# senseBox-MCU_v11.net
KiCad netlist of a schematic drawn in EAGLE
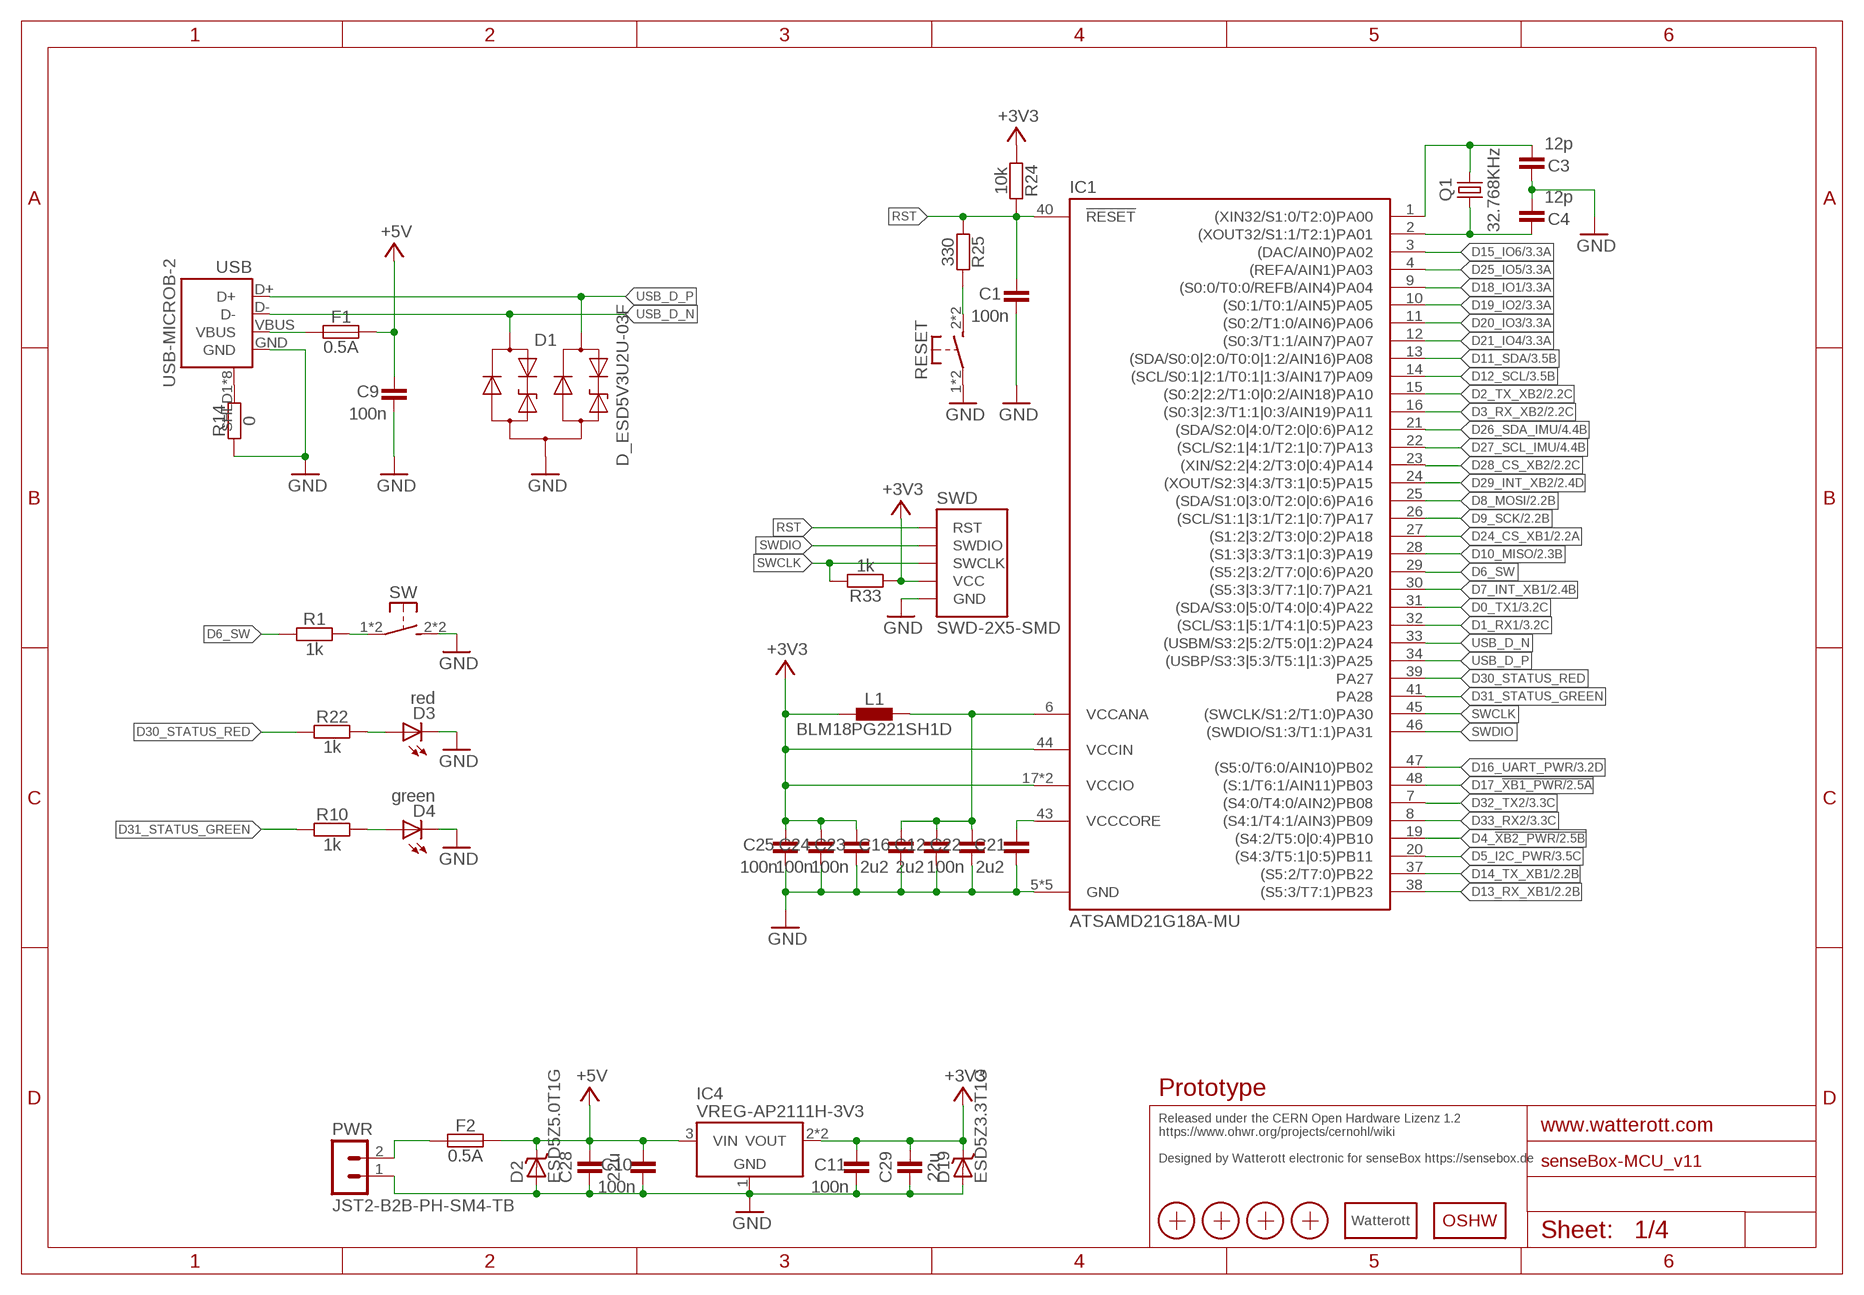
[diagram p0: schematic, sheet 1]
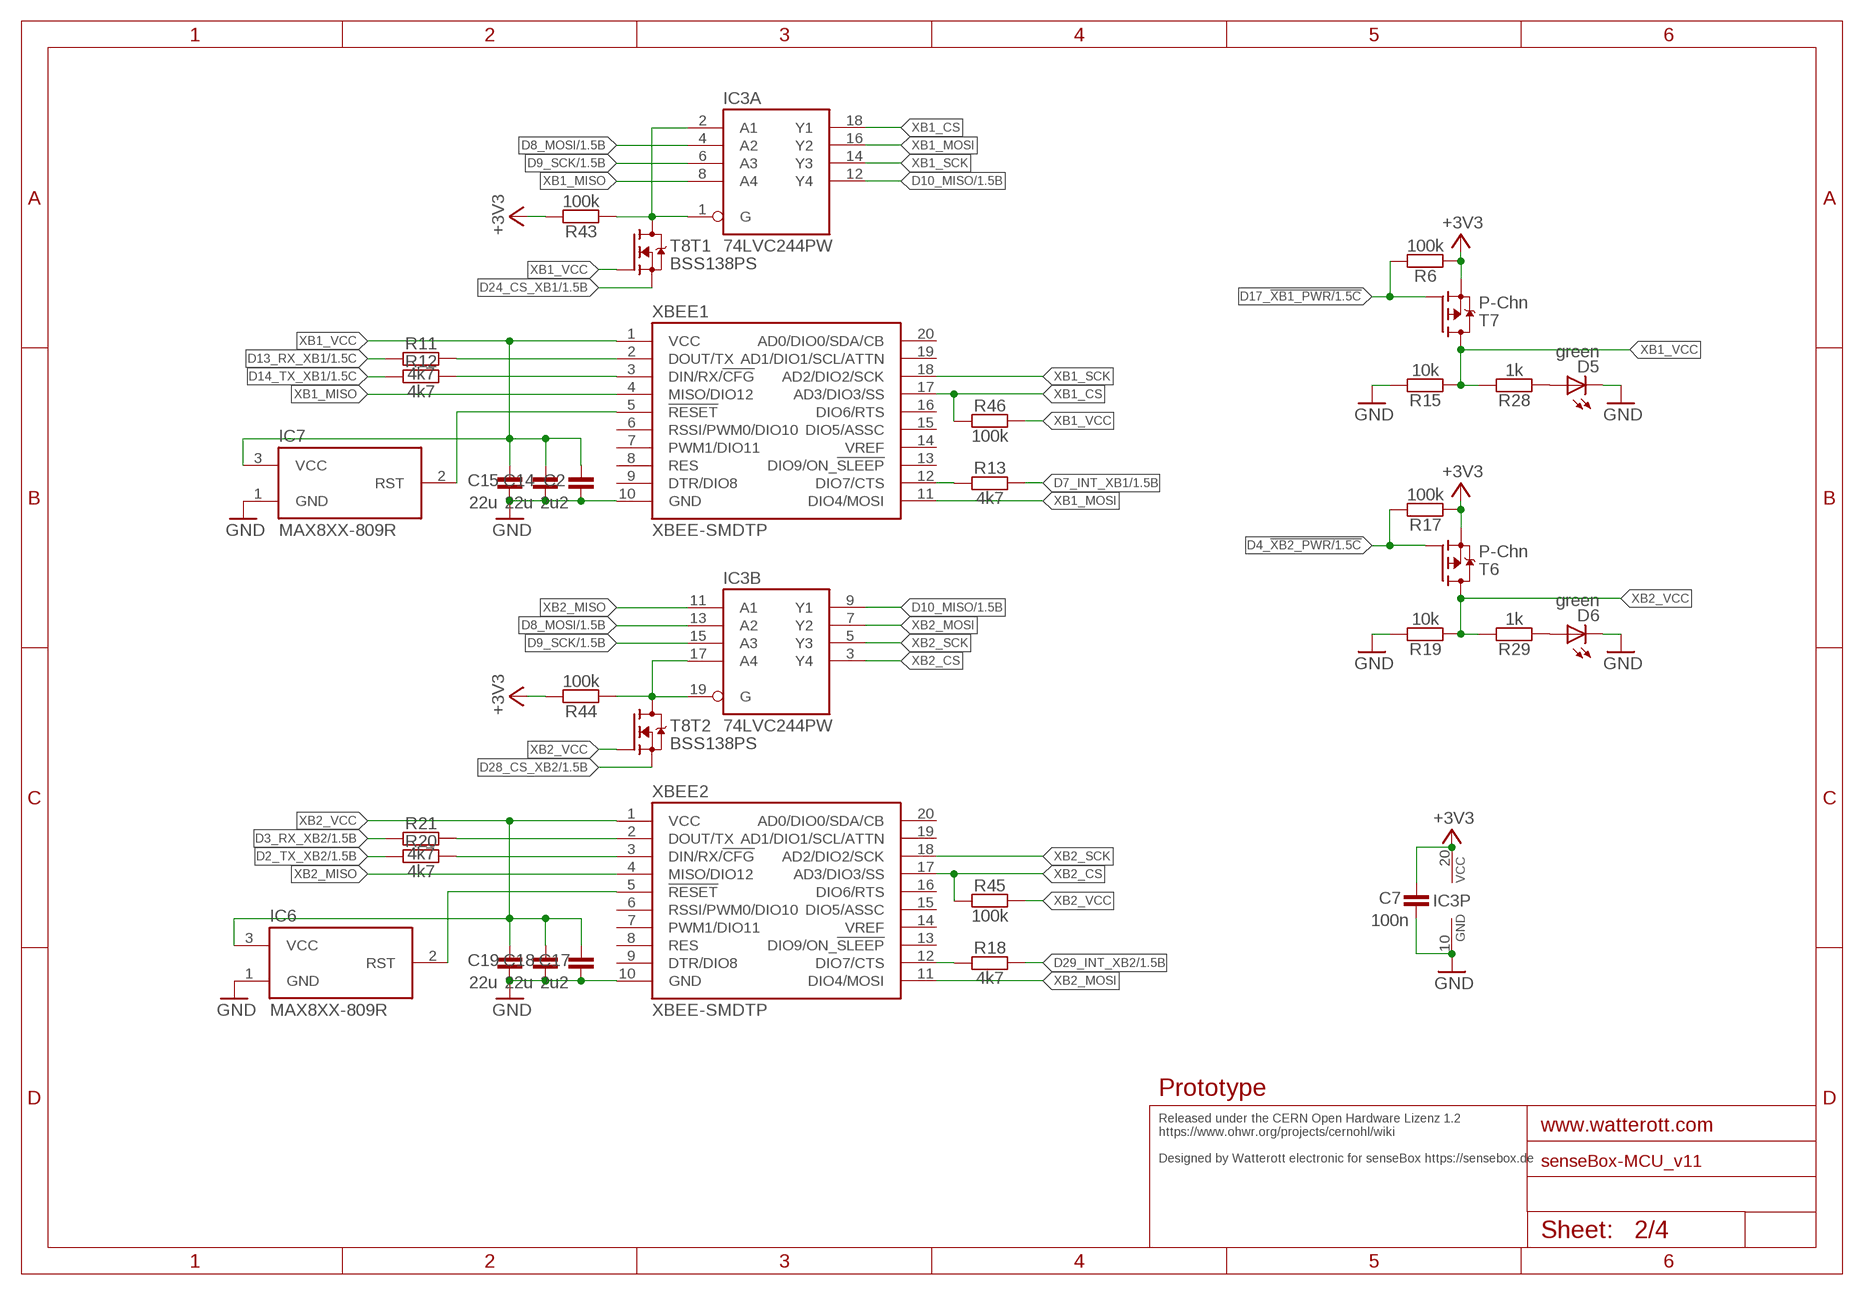
[diagram p1: schematic, sheet 2]
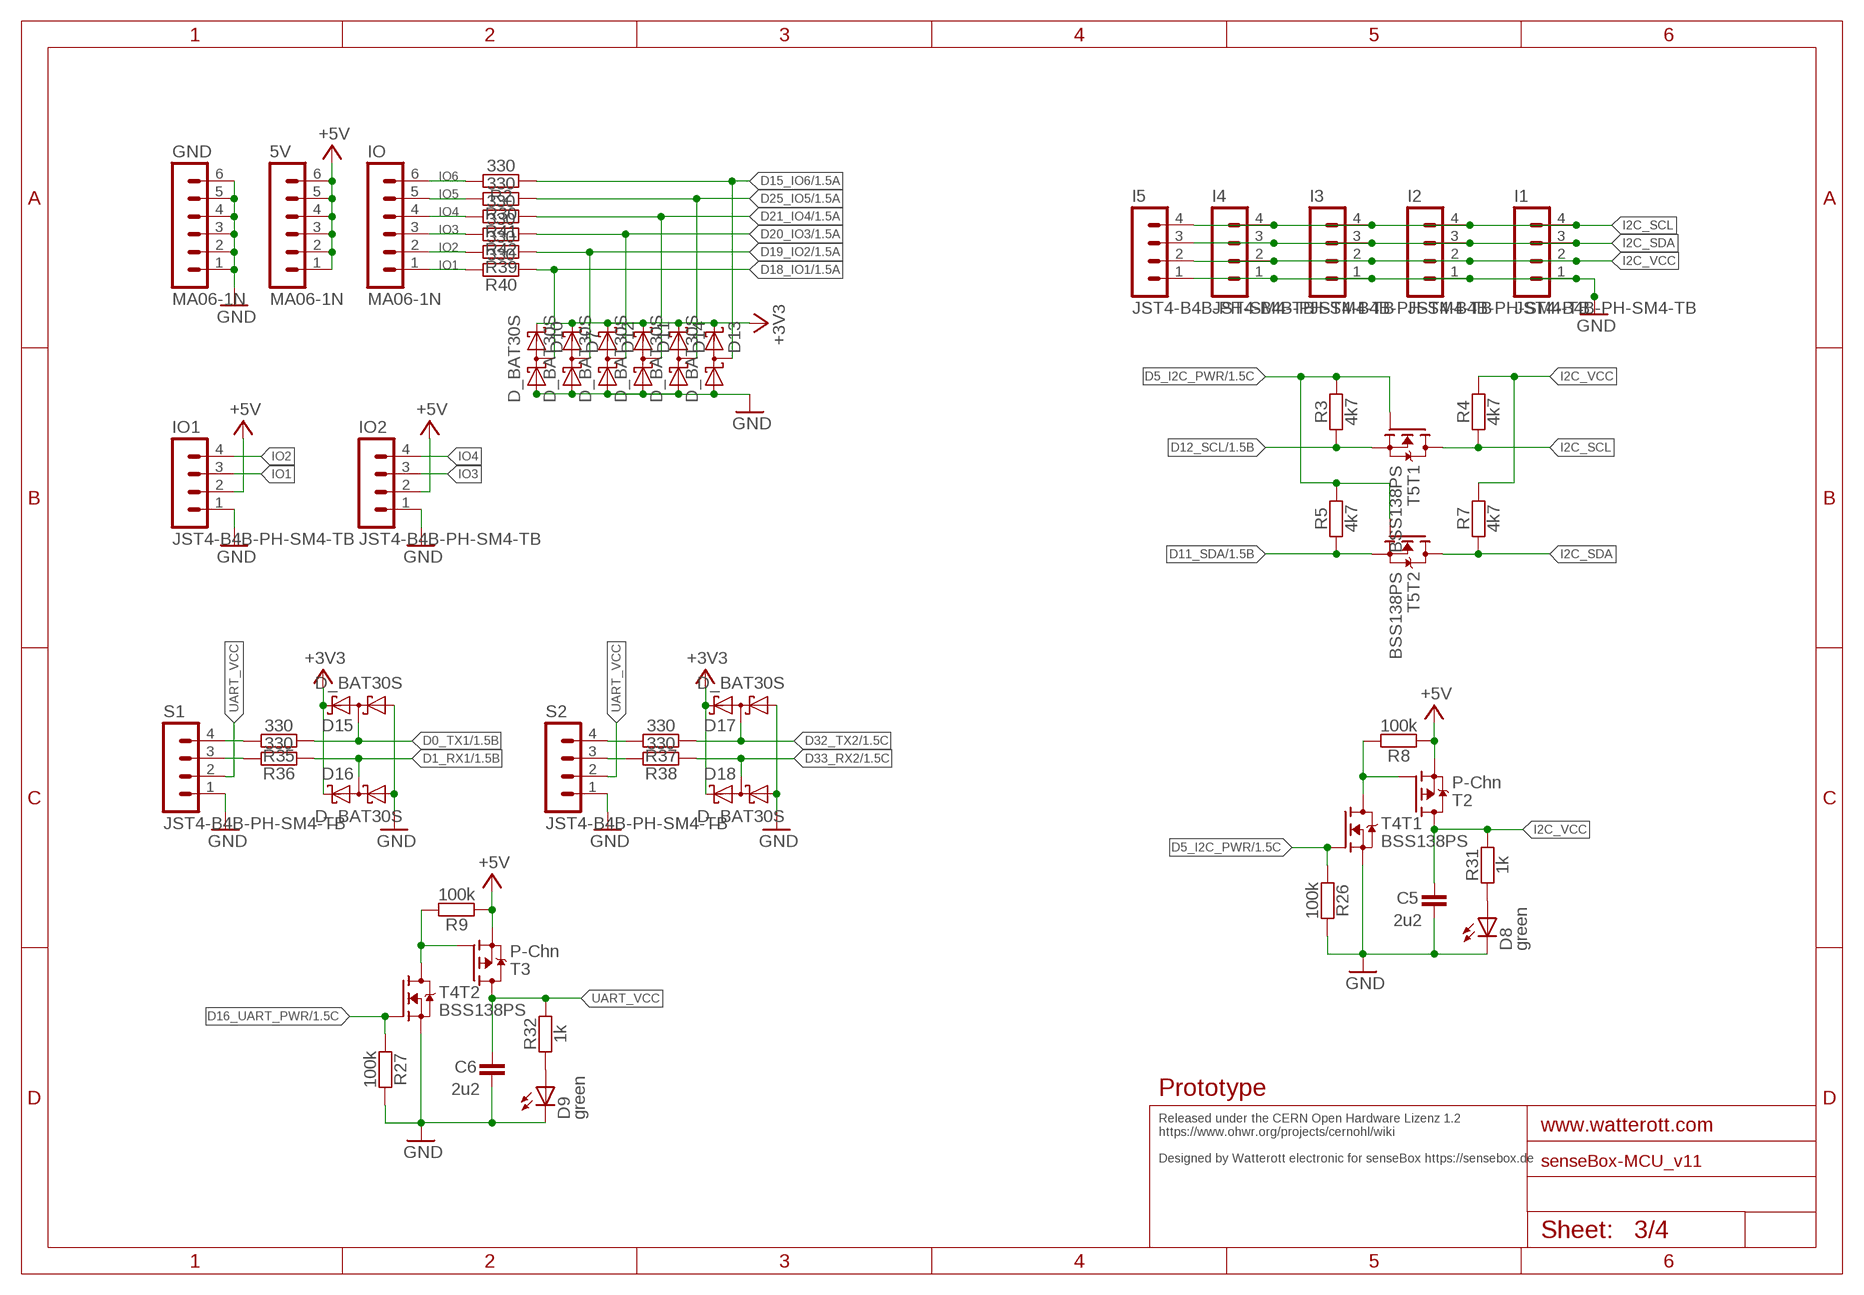
[diagram p2: schematic, sheet 3]
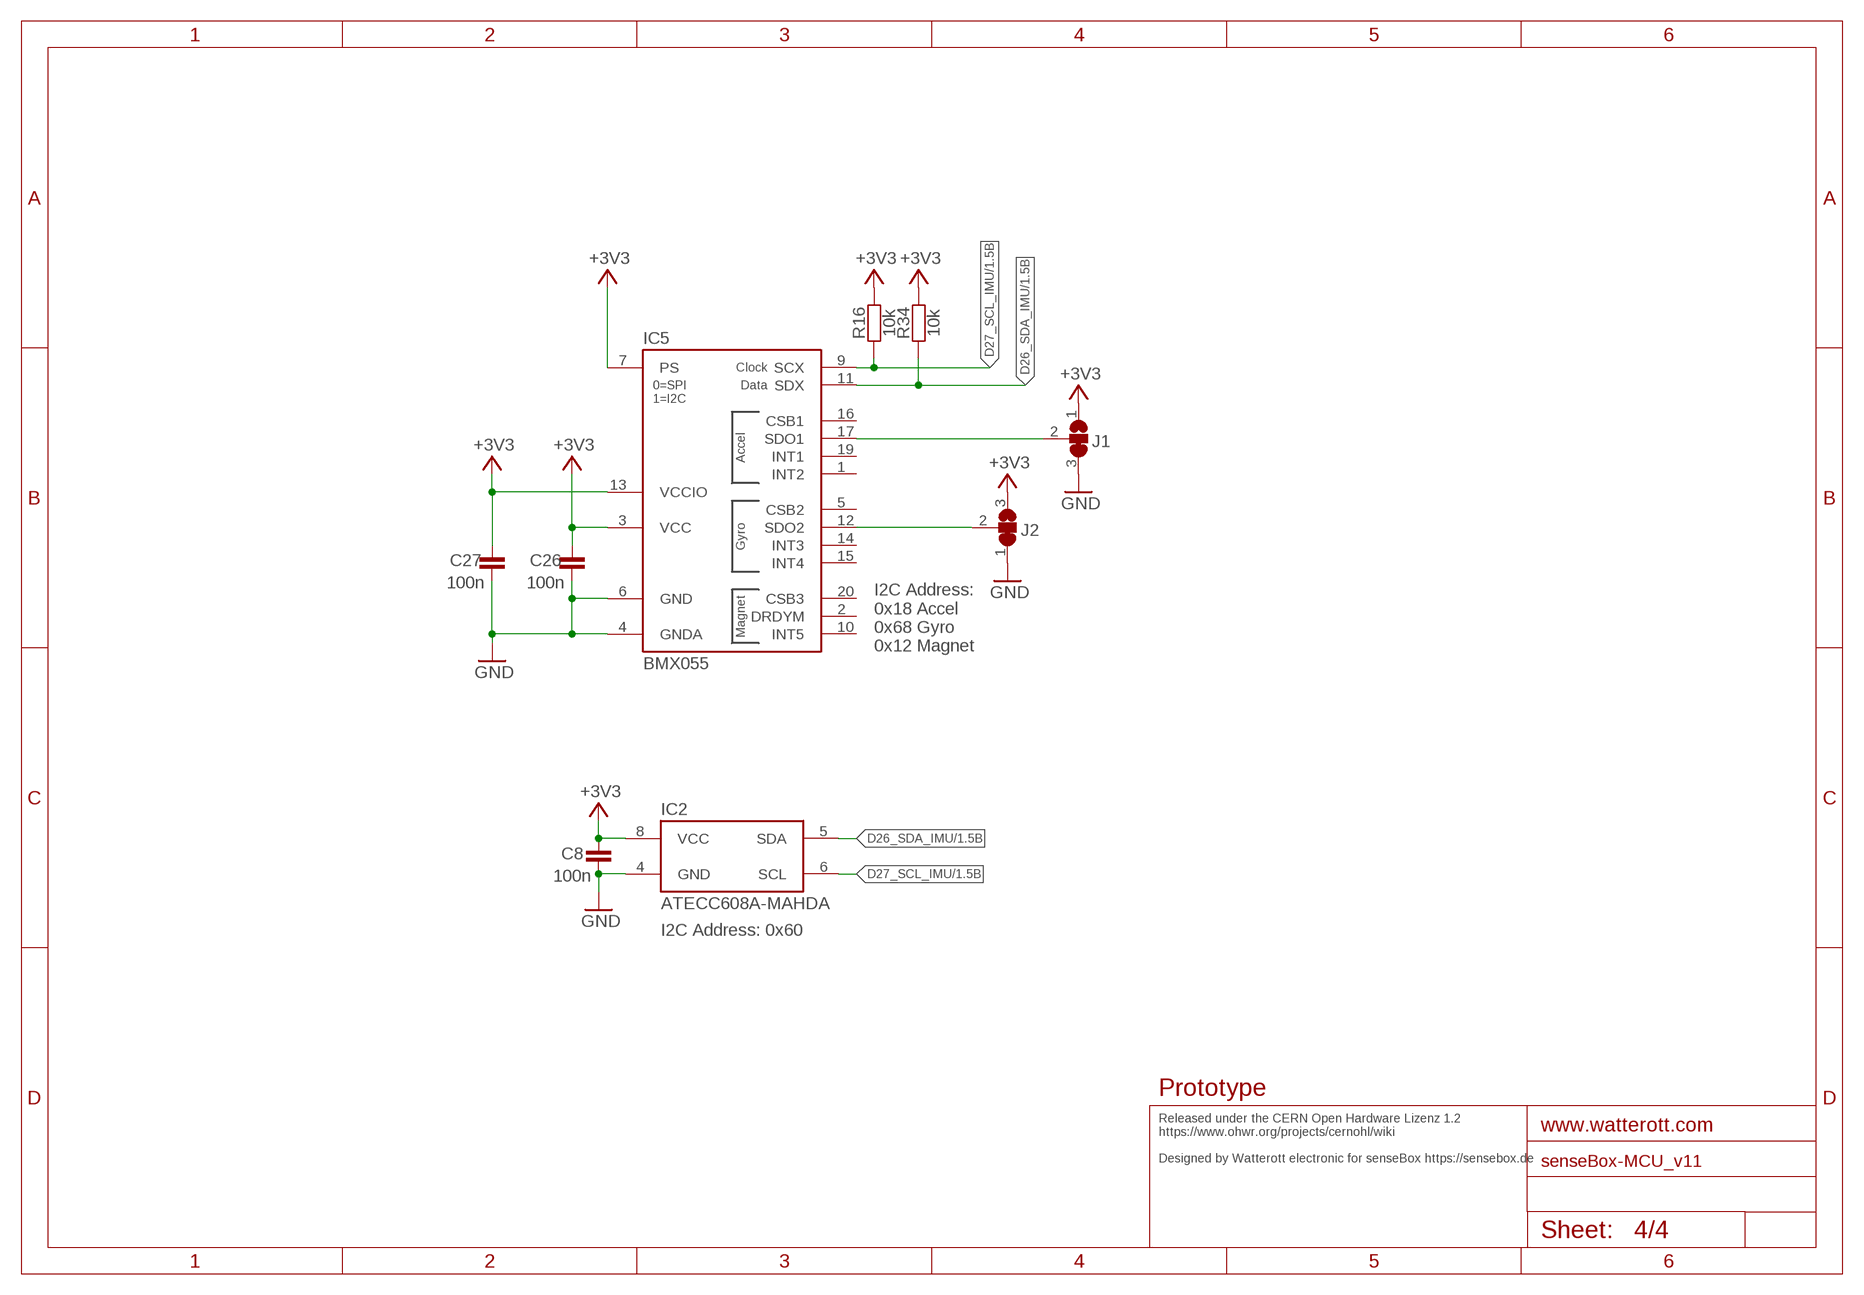
[diagram p3: schematic, sheet 4]

(export (version "E")
  (design (tool "Eeschema 10.0.6"))
  (components
    (comp (ref "C8")
      (value "100n")
      (footprint "eagle-import:C0402")
      (libsource (lib "eagle-import") (part "CAPACITOR-0402"))
    )
    (comp (ref "C26")
      (value "100n")
      (footprint "eagle-import:C0402")
      (libsource (lib "eagle-import") (part "CAPACITOR-0402"))
    )
    (comp (ref "C27")
      (value "100n")
      (footprint "eagle-import:C0402")
      (libsource (lib "eagle-import") (part "CAPACITOR-0402"))
    )
    (comp (ref "IC2")
      (value "ATECC608A-MAHDA")
      (footprint "eagle-import:UDFN8")
      (libsource (lib "eagle-import") (part "ATECC508A-MAHDA"))
    )
    (comp (ref "IC5")
      (value "BMX055")
      (footprint "eagle-import:BMX055")
      (libsource (lib "eagle-import") (part "BMX055"))
    )
    (comp (ref "J1")
      (value "JUMPER3-0402")
      (footprint "eagle-import:JUMPER3-0402")
      (libsource (lib "eagle-import") (part "JUMPER3-0402"))
    )
    (comp (ref "J2")
      (value "JUMPER3-0402")
      (footprint "eagle-import:JUMPER3-0402")
      (libsource (lib "eagle-import") (part "JUMPER3-0402"))
    )
    (comp (ref "R16")
      (value "10k")
      (footprint "eagle-import:C0402")
      (libsource (lib "eagle-import") (part "RESISTOR-0402"))
    )
    (comp (ref "R34")
      (value "10k")
      (footprint "eagle-import:C0402")
      (libsource (lib "eagle-import") (part "RESISTOR-0402"))
    )
    (comp (ref "5V")
      (value "MA06-1N")
      (footprint "eagle-import:MA06-1_N")
      (libsource (lib "eagle-import") (part "MA06-1N"))
    )
    (comp (ref "C5")
      (value "2u2")
      (footprint "eagle-import:C0402")
      (libsource (lib "eagle-import") (part "CAPACITOR-0402"))
    )
    (comp (ref "C6")
      (value "2u2")
      (footprint "eagle-import:C0402")
      (libsource (lib "eagle-import") (part "CAPACITOR-0402"))
    )
    (comp (ref "D7")
      (value "D_BAT30S")
      (footprint "eagle-import:SOT323")
      (libsource (lib "eagle-import") (part "D_BAT30S"))
    )
    (comp (ref "D8")
      (value "green")
      (footprint "eagle-import:C0603")
      (libsource (lib "eagle-import") (part "LED-0603"))
    )
    (comp (ref "D9")
      (value "green")
      (footprint "eagle-import:C0603")
      (libsource (lib "eagle-import") (part "LED-0603"))
    )
    (comp (ref "D10")
      (value "D_BAT30S")
      (footprint "eagle-import:SOT323")
      (libsource (lib "eagle-import") (part "D_BAT30S"))
    )
    (comp (ref "D11")
      (value "D_BAT30S")
      (footprint "eagle-import:SOT323")
      (libsource (lib "eagle-import") (part "D_BAT30S"))
    )
    (comp (ref "D12")
      (value "D_BAT30S")
      (footprint "eagle-import:SOT323")
      (libsource (lib "eagle-import") (part "D_BAT30S"))
    )
    (comp (ref "D13")
      (value "D_BAT30S")
      (footprint "eagle-import:SOT323")
      (libsource (lib "eagle-import") (part "D_BAT30S"))
    )
    (comp (ref "D14")
      (value "D_BAT30S")
      (footprint "eagle-import:SOT323")
      (libsource (lib "eagle-import") (part "D_BAT30S"))
    )
    (comp (ref "D15")
      (value "D_BAT30S")
      (footprint "eagle-import:SOT323")
      (libsource (lib "eagle-import") (part "D_BAT30S"))
    )
    (comp (ref "D16")
      (value "D_BAT30S")
      (footprint "eagle-import:SOT323")
      (libsource (lib "eagle-import") (part "D_BAT30S"))
    )
    (comp (ref "D17")
      (value "D_BAT30S")
      (footprint "eagle-import:SOT323")
      (libsource (lib "eagle-import") (part "D_BAT30S"))
    )
    (comp (ref "D18")
      (value "D_BAT30S")
      (footprint "eagle-import:SOT323")
      (libsource (lib "eagle-import") (part "D_BAT30S"))
    )
    (comp (ref "GND")
      (value "MA06-1N")
      (footprint "eagle-import:MA06-1_N")
      (libsource (lib "eagle-import") (part "MA06-1N"))
    )
    (comp (ref "I1")
      (value "JST4-B4B-PH-SM4-TB")
      (footprint "eagle-import:JST_B4B-PH-SM4-TB")
      (libsource (lib "eagle-import") (part "JST4-B4B-PH-SM4-TB"))
    )
    (comp (ref "I2")
      (value "JST4-B4B-PH-SM4-TB")
      (footprint "eagle-import:JST_B4B-PH-SM4-TB")
      (libsource (lib "eagle-import") (part "JST4-B4B-PH-SM4-TB"))
    )
    (comp (ref "I3")
      (value "JST4-B4B-PH-SM4-TB")
      (footprint "eagle-import:JST_B4B-PH-SM4-TB")
      (libsource (lib "eagle-import") (part "JST4-B4B-PH-SM4-TB"))
    )
    (comp (ref "I4")
      (value "JST4-B4B-PH-SM4-TB")
      (footprint "eagle-import:JST_B4B-PH-SM4-TB")
      (libsource (lib "eagle-import") (part "JST4-B4B-PH-SM4-TB"))
    )
    (comp (ref "I5")
      (value "JST4-B4B-PH-SM4-TB")
      (footprint "eagle-import:JST_B4B-PH-SM4-TB")
      (libsource (lib "eagle-import") (part "JST4-B4B-PH-SM4-TB"))
    )
    (comp (ref "IO")
      (value "MA06-1N")
      (footprint "eagle-import:MA06-1_N")
      (libsource (lib "eagle-import") (part "MA06-1N"))
    )
    (comp (ref "IO1")
      (value "JST4-B4B-PH-SM4-TB")
      (footprint "eagle-import:JST_B4B-PH-SM4-TB")
      (libsource (lib "eagle-import") (part "JST4-B4B-PH-SM4-TB"))
    )
    (comp (ref "IO2")
      (value "JST4-B4B-PH-SM4-TB")
      (footprint "eagle-import:JST_B4B-PH-SM4-TB")
      (libsource (lib "eagle-import") (part "JST4-B4B-PH-SM4-TB"))
    )
    (comp (ref "R2")
      (value "330")
      (footprint "eagle-import:C0402")
      (libsource (lib "eagle-import") (part "RESISTOR-0402"))
    )
    (comp (ref "R3")
      (value "4k7")
      (footprint "eagle-import:C0402")
      (libsource (lib "eagle-import") (part "RESISTOR-0402"))
    )
    (comp (ref "R4")
      (value "4k7")
      (footprint "eagle-import:C0402")
      (libsource (lib "eagle-import") (part "RESISTOR-0402"))
    )
    (comp (ref "R5")
      (value "4k7")
      (footprint "eagle-import:C0402")
      (libsource (lib "eagle-import") (part "RESISTOR-0402"))
    )
    (comp (ref "R7")
      (value "4k7")
      (footprint "eagle-import:C0402")
      (libsource (lib "eagle-import") (part "RESISTOR-0402"))
    )
    (comp (ref "R8")
      (value "100k")
      (footprint "eagle-import:C0402")
      (libsource (lib "eagle-import") (part "RESISTOR-0402"))
    )
    (comp (ref "R9")
      (value "100k")
      (footprint "eagle-import:C0402")
      (libsource (lib "eagle-import") (part "RESISTOR-0402"))
    )
    (comp (ref "R26")
      (value "100k")
      (footprint "eagle-import:C0402")
      (libsource (lib "eagle-import") (part "RESISTOR-0402"))
    )
    (comp (ref "R27")
      (value "100k")
      (footprint "eagle-import:C0402")
      (libsource (lib "eagle-import") (part "RESISTOR-0402"))
    )
    (comp (ref "R30")
      (value "330")
      (footprint "eagle-import:C0402")
      (libsource (lib "eagle-import") (part "RESISTOR-0402"))
    )
    (comp (ref "R31")
      (value "1k")
      (footprint "eagle-import:C0402")
      (libsource (lib "eagle-import") (part "RESISTOR-0402"))
    )
    (comp (ref "R32")
      (value "1k")
      (footprint "eagle-import:C0402")
      (libsource (lib "eagle-import") (part "RESISTOR-0402"))
    )
    (comp (ref "R35")
      (value "330")
      (footprint "eagle-import:C0402")
      (libsource (lib "eagle-import") (part "RESISTOR-0402"))
    )
    (comp (ref "R36")
      (value "330")
      (footprint "eagle-import:C0402")
      (libsource (lib "eagle-import") (part "RESISTOR-0402"))
    )
    (comp (ref "R37")
      (value "330")
      (footprint "eagle-import:C0402")
      (libsource (lib "eagle-import") (part "RESISTOR-0402"))
    )
    (comp (ref "R38")
      (value "330")
      (footprint "eagle-import:C0402")
      (libsource (lib "eagle-import") (part "RESISTOR-0402"))
    )
    (comp (ref "R39")
      (value "330")
      (footprint "eagle-import:C0402")
      (libsource (lib "eagle-import") (part "RESISTOR-0402"))
    )
    (comp (ref "R40")
      (value "330")
      (footprint "eagle-import:C0402")
      (libsource (lib "eagle-import") (part "RESISTOR-0402"))
    )
    (comp (ref "R41")
      (value "330")
      (footprint "eagle-import:C0402")
      (libsource (lib "eagle-import") (part "RESISTOR-0402"))
    )
    (comp (ref "R42")
      (value "330")
      (footprint "eagle-import:C0402")
      (libsource (lib "eagle-import") (part "RESISTOR-0402"))
    )
    (comp (ref "S1")
      (value "JST4-B4B-PH-SM4-TB")
      (footprint "eagle-import:JST_B4B-PH-SM4-TB")
      (libsource (lib "eagle-import") (part "JST4-B4B-PH-SM4-TB"))
    )
    (comp (ref "S2")
      (value "JST4-B4B-PH-SM4-TB")
      (footprint "eagle-import:JST_B4B-PH-SM4-TB")
      (libsource (lib "eagle-import") (part "JST4-B4B-PH-SM4-TB"))
    )
    (comp (ref "T2")
      (value "P-Chn")
      (footprint "eagle-import:SOT23")
      (libsource (lib "eagle-import") (part "MOSFET-P-SOT23"))
    )
    (comp (ref "T3")
      (value "P-Chn")
      (footprint "eagle-import:SOT23")
      (libsource (lib "eagle-import") (part "MOSFET-P-SOT23"))
    )
    (comp (ref "T4")
      (value "BSS138PS")
      (footprint "eagle-import:SOT363")
      (libsource (lib "eagle-import") (part "BSS138PS"))
    )
    (comp (ref "T5")
      (value "BSS138PS")
      (footprint "eagle-import:SOT363")
      (libsource (lib "eagle-import") (part "BSS138PS"))
    )
    (comp (ref "C2")
      (value "2u2")
      (footprint "eagle-import:C0402")
      (libsource (lib "eagle-import") (part "CAPACITOR-0402"))
    )
    (comp (ref "C7")
      (value "100n")
      (footprint "eagle-import:C0402")
      (libsource (lib "eagle-import") (part "CAPACITOR-0402"))
    )
    (comp (ref "C14")
      (value "22u")
      (footprint "eagle-import:C0805")
      (libsource (lib "eagle-import") (part "CAPACITOR-0805"))
    )
    (comp (ref "C15")
      (value "22u")
      (footprint "eagle-import:C0805")
      (libsource (lib "eagle-import") (part "CAPACITOR-0805"))
    )
    (comp (ref "C17")
      (value "2u2")
      (footprint "eagle-import:C0402")
      (libsource (lib "eagle-import") (part "CAPACITOR-0402"))
    )
    (comp (ref "C18")
      (value "22u")
      (footprint "eagle-import:C0805")
      (libsource (lib "eagle-import") (part "CAPACITOR-0805"))
    )
    (comp (ref "C19")
      (value "22u")
      (footprint "eagle-import:C0805")
      (libsource (lib "eagle-import") (part "CAPACITOR-0805"))
    )
    (comp (ref "D5")
      (value "green")
      (footprint "eagle-import:C0603")
      (libsource (lib "eagle-import") (part "LED-0603"))
    )
    (comp (ref "D6")
      (value "green")
      (footprint "eagle-import:C0603")
      (libsource (lib "eagle-import") (part "LED-0603"))
    )
    (comp (ref "IC3")
      (value "74LVC244PW")
      (footprint "eagle-import:TSSOP20")
      (libsource (lib "eagle-import") (part "74244PWLVC"))
    )
    (comp (ref "IC6")
      (value "MAX8XX-809R")
      (footprint "eagle-import:SOT23")
      (libsource (lib "eagle-import") (part "MAX8XX-809R"))
    )
    (comp (ref "IC7")
      (value "MAX8XX-809R")
      (footprint "eagle-import:SOT23")
      (libsource (lib "eagle-import") (part "MAX8XX-809R"))
    )
    (comp (ref "R6")
      (value "100k")
      (footprint "eagle-import:C0402")
      (libsource (lib "eagle-import") (part "RESISTOR-0402"))
    )
    (comp (ref "R11")
      (value "4k7")
      (footprint "eagle-import:C0402")
      (libsource (lib "eagle-import") (part "RESISTOR-0402"))
    )
    (comp (ref "R12")
      (value "4k7")
      (footprint "eagle-import:C0402")
      (libsource (lib "eagle-import") (part "RESISTOR-0402"))
    )
    (comp (ref "R13")
      (value "4k7")
      (footprint "eagle-import:C0402")
      (libsource (lib "eagle-import") (part "RESISTOR-0402"))
    )
    (comp (ref "R15")
      (value "10k")
      (footprint "eagle-import:C0402")
      (libsource (lib "eagle-import") (part "RESISTOR-0402"))
    )
    (comp (ref "R17")
      (value "100k")
      (footprint "eagle-import:C0402")
      (libsource (lib "eagle-import") (part "RESISTOR-0402"))
    )
    (comp (ref "R18")
      (value "4k7")
      (footprint "eagle-import:C0402")
      (libsource (lib "eagle-import") (part "RESISTOR-0402"))
    )
    (comp (ref "R19")
      (value "10k")
      (footprint "eagle-import:C0402")
      (libsource (lib "eagle-import") (part "RESISTOR-0402"))
    )
    (comp (ref "R20")
      (value "4k7")
      (footprint "eagle-import:C0402")
      (libsource (lib "eagle-import") (part "RESISTOR-0402"))
    )
    (comp (ref "R21")
      (value "4k7")
      (footprint "eagle-import:C0402")
      (libsource (lib "eagle-import") (part "RESISTOR-0402"))
    )
    (comp (ref "R28")
      (value "1k")
      (footprint "eagle-import:C0402")
      (libsource (lib "eagle-import") (part "RESISTOR-0402"))
    )
    (comp (ref "R29")
      (value "1k")
      (footprint "eagle-import:C0402")
      (libsource (lib "eagle-import") (part "RESISTOR-0402"))
    )
    (comp (ref "R43")
      (value "100k")
      (footprint "eagle-import:C0402")
      (libsource (lib "eagle-import") (part "RESISTOR-0402"))
    )
    (comp (ref "R44")
      (value "100k")
      (footprint "eagle-import:C0402")
      (libsource (lib "eagle-import") (part "RESISTOR-0402"))
    )
    (comp (ref "R45")
      (value "100k")
      (footprint "eagle-import:C0402")
      (libsource (lib "eagle-import") (part "RESISTOR-0402"))
    )
    (comp (ref "R46")
      (value "100k")
      (footprint "eagle-import:C0402")
      (libsource (lib "eagle-import") (part "RESISTOR-0402"))
    )
    (comp (ref "T6")
      (value "P-Chn")
      (footprint "eagle-import:SOT23")
      (libsource (lib "eagle-import") (part "MOSFET-P-SOT23"))
    )
    (comp (ref "T7")
      (value "P-Chn")
      (footprint "eagle-import:SOT23")
      (libsource (lib "eagle-import") (part "MOSFET-P-SOT23"))
    )
    (comp (ref "T8")
      (value "BSS138PS")
      (footprint "eagle-import:SOT363")
      (libsource (lib "eagle-import") (part "BSS138PS"))
    )
    (comp (ref "XBEE1")
      (value "XBEE-SMDTP")
      (footprint "eagle-import:XBEE_SMD_TP")
      (libsource (lib "eagle-import") (part "XBEE-SMDTP"))
    )
    (comp (ref "XBEE2")
      (value "XBEE-SMDTP")
      (footprint "eagle-import:XBEE_SMD_TP")
      (libsource (lib "eagle-import") (part "XBEE-SMDTP"))
    )
    (comp (ref "C1")
      (value "100n")
      (footprint "eagle-import:C0402")
      (libsource (lib "eagle-import") (part "CAPACITOR-0402"))
    )
    (comp (ref "C3")
      (value "12p")
      (footprint "eagle-import:C0402")
      (libsource (lib "eagle-import") (part "CAPACITOR-0402"))
    )
    (comp (ref "C4")
      (value "12p")
      (footprint "eagle-import:C0402")
      (libsource (lib "eagle-import") (part "CAPACITOR-0402"))
    )
    (comp (ref "C9")
      (value "100n")
      (footprint "eagle-import:C0402")
      (libsource (lib "eagle-import") (part "CAPACITOR-0402"))
    )
    (comp (ref "C10")
      (value "100n")
      (footprint "eagle-import:C0402")
      (libsource (lib "eagle-import") (part "CAPACITOR-0402"))
    )
    (comp (ref "C11")
      (value "100n")
      (footprint "eagle-import:C0402")
      (libsource (lib "eagle-import") (part "CAPACITOR-0402"))
    )
    (comp (ref "C12")
      (value "2u2")
      (footprint "eagle-import:C0402")
      (libsource (lib "eagle-import") (part "CAPACITOR-0402"))
    )
    (comp (ref "C16")
      (value "2u2")
      (footprint "eagle-import:C0402")
      (libsource (lib "eagle-import") (part "CAPACITOR-0402"))
    )
    (comp (ref "C21")
      (value "2u2")
      (footprint "eagle-import:C0402")
      (libsource (lib "eagle-import") (part "CAPACITOR-0402"))
    )
    (comp (ref "C22")
      (value "100n")
      (footprint "eagle-import:C0402")
      (libsource (lib "eagle-import") (part "CAPACITOR-0402"))
    )
    (comp (ref "C23")
      (value "100n")
      (footprint "eagle-import:C0402")
      (libsource (lib "eagle-import") (part "CAPACITOR-0402"))
    )
    (comp (ref "C24")
      (value "100n")
      (footprint "eagle-import:C0402")
      (libsource (lib "eagle-import") (part "CAPACITOR-0402"))
    )
    (comp (ref "C25")
      (value "100n")
      (footprint "eagle-import:C0402")
      (libsource (lib "eagle-import") (part "CAPACITOR-0402"))
    )
    (comp (ref "C28")
      (value "22u")
      (footprint "eagle-import:C0805")
      (libsource (lib "eagle-import") (part "CAPACITOR-0805"))
    )
    (comp (ref "C29")
      (value "22u")
      (footprint "eagle-import:C0805")
      (libsource (lib "eagle-import") (part "CAPACITOR-0805"))
    )
    (comp (ref "D1")
      (value "D_ESD5V3U2U-03F")
      (footprint "eagle-import:SOT723")
      (libsource (lib "eagle-import") (part "D_ESD5V3U2U-03F"))
    )
    (comp (ref "D2")
      (value "ESD5Z5.0T1G")
      (footprint "eagle-import:SOD523")
      (libsource (lib "eagle-import") (part "D_TVS-SOD523"))
    )
    (comp (ref "D3")
      (value "red")
      (footprint "eagle-import:C0603")
      (libsource (lib "eagle-import") (part "LED-0603"))
    )
    (comp (ref "D4")
      (value "green")
      (footprint "eagle-import:C0603")
      (libsource (lib "eagle-import") (part "LED-0603"))
    )
    (comp (ref "D19")
      (value "ESD5Z3.3T1G")
      (footprint "eagle-import:SOD523")
      (libsource (lib "eagle-import") (part "D_TVS-SOD523"))
    )
    (comp (ref "F1")
      (value "0.5A")
      (footprint "eagle-import:C0805")
      (libsource (lib "eagle-import") (part "FUSE-0805"))
    )
    (comp (ref "F2")
      (value "0.5A")
      (footprint "eagle-import:C0805")
      (libsource (lib "eagle-import") (part "FUSE-0805"))
    )
    (comp (ref "IC1")
      (value "ATSAMD21G18A-MU")
      (footprint "eagle-import:QFN48-PAD")
      (libsource (lib "eagle-import") (part "ATSAMD21G18A-MU"))
    )
    (comp (ref "IC4")
      (value "VREG-AP2111H-3V3")
      (footprint "eagle-import:SOT223")
      (libsource (lib "eagle-import") (part "VREG-TS1117CW-3V3"))
    )
    (comp (ref "L1")
      (value "BLM18PG221SH1D")
      (footprint "eagle-import:C0603")
      (libsource (lib "eagle-import") (part "INDUCTOR-0603"))
    )
    (comp (ref "LOGO2")
      (value "OSHW_LOGOX0070")
      (footprint "eagle-import:OSHW_6X70")
      (libsource (lib "eagle-import") (part "OSHW_LOGOX0070"))
    )
    (comp (ref "LOGO3")
      (value "LOGO_SPARK-2")
      (footprint "eagle-import:SPARK_2MM")
      (libsource (lib "eagle-import") (part "LOGO_SPARK-2"))
    )
    (comp (ref "PWR")
      (value "JST2-B2B-PH-SM4-TB")
      (footprint "eagle-import:JST_B2B-PH-SM4-TB")
      (libsource (lib "eagle-import") (part "JST2-B2B-PH-SM4-TB"))
    )
    (comp (ref "Q1")
      (value "32.768KHz")
      (footprint "eagle-import:CRYSTAL_ZM315")
      (libsource (lib "eagle-import") (part "CRYSTAL-ZM315"))
    )
    (comp (ref "R1")
      (value "1k")
      (footprint "eagle-import:C0402")
      (libsource (lib "eagle-import") (part "RESISTOR-0402"))
    )
    (comp (ref "R10")
      (value "1k")
      (footprint "eagle-import:C0402")
      (libsource (lib "eagle-import") (part "RESISTOR-0402"))
    )
    (comp (ref "R14")
      (value "0")
      (footprint "eagle-import:C0402")
      (libsource (lib "eagle-import") (part "RESISTOR-0402"))
    )
    (comp (ref "R22")
      (value "1k")
      (footprint "eagle-import:C0402")
      (libsource (lib "eagle-import") (part "RESISTOR-0402"))
    )
    (comp (ref "R24")
      (value "10k")
      (footprint "eagle-import:C0402")
      (libsource (lib "eagle-import") (part "RESISTOR-0402"))
    )
    (comp (ref "R25")
      (value "330")
      (footprint "eagle-import:C0402")
      (libsource (lib "eagle-import") (part "RESISTOR-0402"))
    )
    (comp (ref "R33")
      (value "1k")
      (footprint "eagle-import:C0402")
      (libsource (lib "eagle-import") (part "RESISTOR-0402"))
    )
    (comp (ref "RESET")
      (value "SW-TACTILE-TL3305")
      (footprint "eagle-import:TL3305")
      (libsource (lib "eagle-import") (part "SW-TACTILE-TL3305"))
    )
    (comp (ref "SW")
      (value "SW-TACTILE-TL3305")
      (footprint "eagle-import:TL3305")
      (libsource (lib "eagle-import") (part "SW-TACTILE-TL3305"))
    )
    (comp (ref "SWD")
      (value "SWD-2X5-SMD")
      (footprint "eagle-import:SWD-2X5_SMD")
      (libsource (lib "eagle-import") (part "SWD-2X5-SMD"))
    )
    (comp (ref "USB")
      (value "USB-MICROB-2")
      (footprint "eagle-import:USB-MICROB-10118194")
      (libsource (lib "eagle-import") (part "USB-MICROB-2"))
    )
    (comp (ref "X1")
      (value "PASSER-07")
      (footprint "eagle-import:PASSER_07MM")
      (libsource (lib "eagle-import") (part "PASSER-07"))
    )
    (comp (ref "X2")
      (value "PASSER-07")
      (footprint "eagle-import:PASSER_07MM")
      (libsource (lib "eagle-import") (part "PASSER-07"))
    )
    (comp (ref "X3")
      (value "PASSER-07")
      (footprint "eagle-import:PASSER_07MM")
      (libsource (lib "eagle-import") (part "PASSER-07"))
    )
    (comp (ref "X4")
      (value "PASSER-07")
      (footprint "eagle-import:PASSER_07MM")
      (libsource (lib "eagle-import") (part "PASSER-07"))
    )
  )
  (nets
    (net (code "1") (name "+3V3") (class "Default")
      (node (ref "C11") (pin "2") (pinfunction "2_2") (pintype "passive"))
      (node (ref "C23") (pin "2") (pinfunction "2_2") (pintype "passive"))
      (node (ref "C24") (pin "2") (pinfunction "2_2") (pintype "passive"))
      (node (ref "C25") (pin "2") (pinfunction "2_2") (pintype "passive"))
      (node (ref "C26") (pin "2") (pinfunction "2_2") (pintype "passive"))
      (node (ref "C27") (pin "2") (pinfunction "2_2") (pintype "passive"))
      (node (ref "C29") (pin "2") (pinfunction "2_2") (pintype "passive"))
      (node (ref "C7") (pin "2") (pinfunction "2_2") (pintype "passive"))
      (node (ref "C8") (pin "2") (pinfunction "2_2") (pintype "passive"))
      (node (ref "D10") (pin "2") (pinfunction "C_2") (pintype "passive"))
      (node (ref "D11") (pin "2") (pinfunction "C_2") (pintype "passive"))
      (node (ref "D12") (pin "2") (pinfunction "C_2") (pintype "passive"))
      (node (ref "D13") (pin "2") (pinfunction "C_2") (pintype "passive"))
      (node (ref "D14") (pin "2") (pinfunction "C_2") (pintype "passive"))
      (node (ref "D15") (pin "2") (pinfunction "C_2") (pintype "passive"))
      (node (ref "D16") (pin "2") (pinfunction "C_2") (pintype "passive"))
      (node (ref "D17") (pin "2") (pinfunction "C_2") (pintype "passive"))
      (node (ref "D18") (pin "2") (pinfunction "C_2") (pintype "passive"))
      (node (ref "D19") (pin "C") (pinfunction "C_C") (pintype "passive"))
      (node (ref "D7") (pin "2") (pinfunction "C_2") (pintype "passive"))
      (node (ref "IC1") (pin "17") (pinfunction "VCCIO_17") (pintype "power_in"))
      (node (ref "IC1") (pin "36") (pinfunction "VCCIO_36") (pintype "power_in"))
      (node (ref "IC1") (pin "44") (pinfunction "VCCIN_44") (pintype "power_in"))
      (node (ref "IC2") (pin "8") (pinfunction "VCC_8") (pintype "power_in"))
      (node (ref "IC3") (pin "20") (pinfunction "VCC_20") (pintype "power_in"))
      (node (ref "IC4") (pin "2") (pinfunction "VOUT_2") (pintype "power_in"))
      (node (ref "IC4") (pin "4") (pinfunction "VOUT_4") (pintype "power_in"))
      (node (ref "IC5") (pin "13") (pinfunction "VCCIO_13") (pintype "power_in"))
      (node (ref "IC5") (pin "3") (pinfunction "VCC_3") (pintype "power_in"))
      (node (ref "IC5") (pin "7") (pinfunction "PS_7") (pintype "input"))
      (node (ref "J1") (pin "1") (pinfunction "1_1") (pintype "passive"))
      (node (ref "J2") (pin "3") (pinfunction "3_3") (pintype "passive"))
      (node (ref "L1") (pin "1") (pinfunction "1_1") (pintype "passive"))
      (node (ref "R16") (pin "2") (pinfunction "2_2") (pintype "passive"))
      (node (ref "R17") (pin "1") (pinfunction "1_1") (pintype "passive"))
      (node (ref "R24") (pin "1") (pinfunction "1_1") (pintype "passive"))
      (node (ref "R33") (pin "1") (pinfunction "1_1") (pintype "passive"))
      (node (ref "R34") (pin "2") (pinfunction "2_2") (pintype "passive"))
      (node (ref "R43") (pin "2") (pinfunction "2_2") (pintype "passive"))
      (node (ref "R44") (pin "2") (pinfunction "2_2") (pintype "passive"))
      (node (ref "R6") (pin "1") (pinfunction "1_1") (pintype "passive"))
      (node (ref "SWD") (pin "VCC") (pinfunction "VCC_VCC") (pintype "power_in"))
      (node (ref "T6") (pin "2") (pinfunction "S_2") (pintype "passive"))
      (node (ref "T7") (pin "2") (pinfunction "S_2") (pintype "passive"))
    )
    (net (code "2") (name "+5V") (class "Default")
      (node (ref "5V") (pin "1") (pinfunction "1_1") (pintype "passive"))
      (node (ref "5V") (pin "2") (pinfunction "2_2") (pintype "passive"))
      (node (ref "5V") (pin "3") (pinfunction "3_3") (pintype "passive"))
      (node (ref "5V") (pin "4") (pinfunction "4_4") (pintype "passive"))
      (node (ref "5V") (pin "5") (pinfunction "5_5") (pintype "passive"))
      (node (ref "5V") (pin "6") (pinfunction "6_6") (pintype "passive"))
      (node (ref "C10") (pin "2") (pinfunction "2_2") (pintype "passive"))
      (node (ref "C28") (pin "2") (pinfunction "2_2") (pintype "passive"))
      (node (ref "C9") (pin "2") (pinfunction "2_2") (pintype "passive"))
      (node (ref "D2") (pin "C") (pinfunction "C_C") (pintype "passive"))
      (node (ref "F1") (pin "2") (pinfunction "2_2") (pintype "passive"))
      (node (ref "F2") (pin "2") (pinfunction "2_2") (pintype "passive"))
      (node (ref "IC4") (pin "3") (pinfunction "VIN_3") (pintype "power_in"))
      (node (ref "IO1") (pin "2") (pinfunction "2_2") (pintype "passive"))
      (node (ref "IO2") (pin "2") (pinfunction "2_2") (pintype "passive"))
      (node (ref "R8") (pin "1") (pinfunction "1_1") (pintype "passive"))
      (node (ref "R9") (pin "1") (pinfunction "1_1") (pintype "passive"))
      (node (ref "T2") (pin "2") (pinfunction "S_2") (pintype "passive"))
      (node (ref "T3") (pin "2") (pinfunction "S_2") (pintype "passive"))
    )
    (net (code "3") (name "D0_TX1") (class "Default")
      (node (ref "D15") (pin "3") (pinfunction "CA_3") (pintype "passive"))
      (node (ref "IC1") (pin "31") (pinfunction "(SDA/S3:0|5:0/T4:0|0:4)PA22_31") (pintype "bidirectional"))
      (node (ref "R35") (pin "1") (pinfunction "1_1") (pintype "passive"))
    )
    (net (code "4") (name "D1_RX1") (class "Default")
      (node (ref "D16") (pin "3") (pinfunction "CA_3") (pintype "passive"))
      (node (ref "IC1") (pin "32") (pinfunction "(SCL/S3:1|5:1/T4:1|0:5)PA23_32") (pintype "bidirectional"))
      (node (ref "R36") (pin "1") (pinfunction "1_1") (pintype "passive"))
    )
    (net (code "5") (name "D2_TX_XB2") (class "Default")
      (node (ref "IC1") (pin "15") (pinfunction "(S0:2|2:2/T1:0|0:2/AIN18)PA10_15") (pintype "bidirectional"))
      (node (ref "R20") (pin "1") (pinfunction "1_1") (pintype "passive"))
    )
    (net (code "6") (name "D3_RX_XB2") (class "Default")
      (node (ref "IC1") (pin "16") (pinfunction "(S0:3|2:3/T1:1|0:3/AIN19)PA11_16") (pintype "bidirectional"))
      (node (ref "R21") (pin "1") (pinfunction "1_1") (pintype "passive"))
    )
    (net (code "7") (name "D4_~{XB2_PWR}") (class "Default")
      (node (ref "IC1") (pin "19") (pinfunction "(S4:2/T5:0|0:4)PB10_19") (pintype "bidirectional"))
      (node (ref "R17") (pin "2") (pinfunction "2_2") (pintype "passive"))
      (node (ref "T6") (pin "1") (pinfunction "G_1") (pintype "passive"))
    )
    (net (code "8") (name "D5_I2C_PWR") (class "Default")
      (node (ref "IC1") (pin "20") (pinfunction "(S4:3/T5:1|0:5)PB11_20") (pintype "bidirectional"))
      (node (ref "R26") (pin "1") (pinfunction "1_1") (pintype "passive"))
      (node (ref "R3") (pin "2") (pinfunction "2_2") (pintype "passive"))
      (node (ref "R5") (pin "2") (pinfunction "2_2") (pintype "passive"))
      (node (ref "T4") (pin "2") (pinfunction "G_2") (pintype "passive"))
      (node (ref "T5") (pin "2") (pinfunction "G_2") (pintype "passive"))
      (node (ref "T5") (pin "5") (pinfunction "G_5") (pintype "passive"))
    )
    (net (code "9") (name "D6_SW") (class "Default")
      (node (ref "IC1") (pin "29") (pinfunction "(S5:2|3:2/T7:0|0:6)PA20_29") (pintype "bidirectional"))
      (node (ref "R1") (pin "1") (pinfunction "1_1") (pintype "passive"))
    )
    (net (code "10") (name "D7_INT_XB1") (class "Default")
      (node (ref "IC1") (pin "30") (pinfunction "(S5:3|3:3/T7:1|0:7)PA21_30") (pintype "bidirectional"))
      (node (ref "R13") (pin "2") (pinfunction "2_2") (pintype "passive"))
    )
    (net (code "11") (name "D8_MOSI") (class "Default")
      (node (ref "IC1") (pin "25") (pinfunction "(SDA/S1:0|3:0/T2:0|0:6)PA16_25") (pintype "bidirectional"))
      (node (ref "IC3") (pin "13") (pinfunction "A2_13") (pintype "input"))
      (node (ref "IC3") (pin "4") (pinfunction "A2_4") (pintype "input"))
    )
    (net (code "12") (name "D9_SCK") (class "Default")
      (node (ref "IC1") (pin "26") (pinfunction "(SCL/S1:1|3:1/T2:1|0:7)PA17_26") (pintype "bidirectional"))
      (node (ref "IC3") (pin "15") (pinfunction "A3_15") (pintype "input"))
      (node (ref "IC3") (pin "6") (pinfunction "A3_6") (pintype "input"))
    )
    (net (code "13") (name "D10_MISO") (class "Default")
      (node (ref "IC1") (pin "28") (pinfunction "(S1:3|3:3/T3:1|0:3)PA19_28") (pintype "bidirectional"))
      (node (ref "IC3") (pin "12") (pinfunction "Y4_12") (pintype "tri_state"))
      (node (ref "IC3") (pin "9") (pinfunction "Y1_9") (pintype "tri_state"))
    )
    (net (code "14") (name "D11_SDA") (class "Default")
      (node (ref "IC1") (pin "13") (pinfunction "(SDA/S0:0|2:0/T0:0|1:2/AIN16)PA08_13") (pintype "bidirectional"))
      (node (ref "R5") (pin "1") (pinfunction "1_1") (pintype "passive"))
      (node (ref "T5") (pin "4") (pinfunction "S_4") (pintype "passive"))
    )
    (net (code "15") (name "D12_SCL") (class "Default")
      (node (ref "IC1") (pin "14") (pinfunction "(SCL/S0:1|2:1/T0:1|1:3/AIN17)PA09_14") (pintype "bidirectional"))
      (node (ref "R3") (pin "1") (pinfunction "1_1") (pintype "passive"))
      (node (ref "T5") (pin "1") (pinfunction "S_1") (pintype "passive"))
    )
    (net (code "16") (name "D13_RX_XB1") (class "Default")
      (node (ref "IC1") (pin "38") (pinfunction "(S5:3/T7:1)PB23_38") (pintype "bidirectional"))
      (node (ref "R11") (pin "1") (pinfunction "1_1") (pintype "passive"))
    )
    (net (code "17") (name "D14_TX_XB1") (class "Default")
      (node (ref "IC1") (pin "37") (pinfunction "(S5:2/T7:0)PB22_37") (pintype "bidirectional"))
      (node (ref "R12") (pin "1") (pinfunction "1_1") (pintype "passive"))
    )
    (net (code "18") (name "D15_IO6") (class "Default")
      (node (ref "D13") (pin "3") (pinfunction "CA_3") (pintype "passive"))
      (node (ref "IC1") (pin "3") (pinfunction "(DAC/AIN0)PA02_3") (pintype "bidirectional"))
      (node (ref "R2") (pin "1") (pinfunction "1_1") (pintype "passive"))
    )
    (net (code "19") (name "D16_UART_PWR") (class "Default")
      (node (ref "IC1") (pin "47") (pinfunction "(S5:0/T6:0/AIN10)PB02_47") (pintype "bidirectional"))
      (node (ref "R27") (pin "1") (pinfunction "1_1") (pintype "passive"))
      (node (ref "T4") (pin "5") (pinfunction "G_5") (pintype "passive"))
    )
    (net (code "20") (name "D17_~{XB1_PWR}") (class "Default")
      (node (ref "IC1") (pin "48") (pinfunction "(S:1/T6:1/AIN11)PB03_48") (pintype "bidirectional"))
      (node (ref "R6") (pin "2") (pinfunction "2_2") (pintype "passive"))
      (node (ref "T7") (pin "1") (pinfunction "G_1") (pintype "passive"))
    )
    (net (code "21") (name "D18_IO1") (class "Default")
      (node (ref "D10") (pin "3") (pinfunction "CA_3") (pintype "passive"))
      (node (ref "IC1") (pin "9") (pinfunction "(S0:0/T0:0/REFB/AIN4)PA04_9") (pintype "bidirectional"))
      (node (ref "R40") (pin "1") (pinfunction "1_1") (pintype "passive"))
    )
    (net (code "22") (name "D19_IO2") (class "Default")
      (node (ref "D7") (pin "3") (pinfunction "CA_3") (pintype "passive"))
      (node (ref "IC1") (pin "10") (pinfunction "(S0:1/T0:1/AIN5)PA05_10") (pintype "bidirectional"))
      (node (ref "R39") (pin "1") (pinfunction "1_1") (pintype "passive"))
    )
    (net (code "23") (name "D20_IO3") (class "Default")
      (node (ref "D12") (pin "3") (pinfunction "CA_3") (pintype "passive"))
      (node (ref "IC1") (pin "11") (pinfunction "(S0:2/T1:0/AIN6)PA06_11") (pintype "bidirectional"))
      (node (ref "R42") (pin "1") (pinfunction "1_1") (pintype "passive"))
    )
    (net (code "24") (name "D21_IO4") (class "Default")
      (node (ref "D11") (pin "3") (pinfunction "CA_3") (pintype "passive"))
      (node (ref "IC1") (pin "12") (pinfunction "(S0:3/T1:1/AIN7)PA07_12") (pintype "bidirectional"))
      (node (ref "R41") (pin "1") (pinfunction "1_1") (pintype "passive"))
    )
    (net (code "25") (name "D24_CS_XB1") (class "Default")
      (node (ref "IC1") (pin "27") (pinfunction "(S1:2|3:2/T3:0|0:2)PA18_27") (pintype "bidirectional"))
      (node (ref "T8") (pin "1") (pinfunction "S_1") (pintype "passive"))
    )
    (net (code "26") (name "D25_IO5") (class "Default")
      (node (ref "D14") (pin "3") (pinfunction "CA_3") (pintype "passive"))
      (node (ref "IC1") (pin "4") (pinfunction "(REFA/AIN1)PA03_4") (pintype "bidirectional"))
      (node (ref "R30") (pin "1") (pinfunction "1_1") (pintype "passive"))
    )
    (net (code "27") (name "D26_SDA_IMU") (class "Default")
      (node (ref "IC1") (pin "21") (pinfunction "(SDA/S2:0|4:0/T2:0|0:6)PA12_21") (pintype "bidirectional"))
      (node (ref "IC2") (pin "5") (pinfunction "SDA_5") (pintype "bidirectional"))
      (node (ref "IC5") (pin "11") (pinfunction "SDX_11") (pintype "bidirectional"))
      (node (ref "R34") (pin "1") (pinfunction "1_1") (pintype "passive"))
    )
    (net (code "28") (name "D27_SCL_IMU") (class "Default")
      (node (ref "IC1") (pin "22") (pinfunction "(SCL/S2:1|4:1/T2:1|0:7)PA13_22") (pintype "bidirectional"))
      (node (ref "IC2") (pin "6") (pinfunction "SCL_6") (pintype "bidirectional"))
      (node (ref "IC5") (pin "9") (pinfunction "SCX_9") (pintype "bidirectional"))
      (node (ref "R16") (pin "1") (pinfunction "1_1") (pintype "passive"))
    )
    (net (code "29") (name "D28_CS_XB2") (class "Default")
      (node (ref "IC1") (pin "23") (pinfunction "(XIN/S2:2|4:2/T3:0|0:4)PA14_23") (pintype "bidirectional"))
      (node (ref "T8") (pin "4") (pinfunction "S_4") (pintype "passive"))
    )
    (net (code "30") (name "D29_INT_XB2") (class "Default")
      (node (ref "IC1") (pin "24") (pinfunction "(XOUT/S2:3|4:3/T3:1|0:5)PA15_24") (pintype "bidirectional"))
      (node (ref "R18") (pin "2") (pinfunction "2_2") (pintype "passive"))
    )
    (net (code "31") (name "D30_STATUS_RED") (class "Default")
      (node (ref "IC1") (pin "39") (pinfunction "PA27_39") (pintype "bidirectional"))
      (node (ref "R22") (pin "1") (pinfunction "1_1") (pintype "passive"))
    )
    (net (code "32") (name "D31_STATUS_GREEN") (class "Default")
      (node (ref "IC1") (pin "41") (pinfunction "PA28_41") (pintype "bidirectional"))
      (node (ref "R10") (pin "1") (pinfunction "1_1") (pintype "passive"))
    )
    (net (code "33") (name "D32_TX2") (class "Default")
      (node (ref "D17") (pin "3") (pinfunction "CA_3") (pintype "passive"))
      (node (ref "IC1") (pin "7") (pinfunction "(S4:0/T4:0/AIN2)PB08_7") (pintype "bidirectional"))
      (node (ref "R37") (pin "1") (pinfunction "1_1") (pintype "passive"))
    )
    (net (code "34") (name "D33_RX2") (class "Default")
      (node (ref "D18") (pin "3") (pinfunction "CA_3") (pintype "passive"))
      (node (ref "IC1") (pin "8") (pinfunction "(S4:1/T4:1/AIN3)PB09_8") (pintype "bidirectional"))
      (node (ref "R38") (pin "1") (pinfunction "1_1") (pintype "passive"))
    )
    (net (code "35") (name "GND") (class "Default")
      (node (ref "C1") (pin "1") (pinfunction "1_1") (pintype "passive"))
      (node (ref "C10") (pin "1") (pinfunction "1_1") (pintype "passive"))
      (node (ref "C11") (pin "1") (pinfunction "1_1") (pintype "passive"))
      (node (ref "C12") (pin "1") (pinfunction "1_1") (pintype "passive"))
      (node (ref "C14") (pin "1") (pinfunction "1_1") (pintype "passive"))
      (node (ref "C15") (pin "1") (pinfunction "1_1") (pintype "passive"))
      (node (ref "C16") (pin "1") (pinfunction "1_1") (pintype "passive"))
      (node (ref "C17") (pin "1") (pinfunction "1_1") (pintype "passive"))
      (node (ref "C18") (pin "1") (pinfunction "1_1") (pintype "passive"))
      (node (ref "C19") (pin "1") (pinfunction "1_1") (pintype "passive"))
      (node (ref "C2") (pin "1") (pinfunction "1_1") (pintype "passive"))
      (node (ref "C21") (pin "1") (pinfunction "1_1") (pintype "passive"))
      (node (ref "C22") (pin "1") (pinfunction "1_1") (pintype "passive"))
      (node (ref "C23") (pin "1") (pinfunction "1_1") (pintype "passive"))
      (node (ref "C24") (pin "1") (pinfunction "1_1") (pintype "passive"))
      (node (ref "C25") (pin "1") (pinfunction "1_1") (pintype "passive"))
      (node (ref "C26") (pin "1") (pinfunction "1_1") (pintype "passive"))
      (node (ref "C27") (pin "1") (pinfunction "1_1") (pintype "passive"))
      (node (ref "C28") (pin "1") (pinfunction "1_1") (pintype "passive"))
      (node (ref "C29") (pin "1") (pinfunction "1_1") (pintype "passive"))
      (node (ref "C3") (pin "2") (pinfunction "2_2") (pintype "passive"))
      (node (ref "C4") (pin "1") (pinfunction "1_1") (pintype "passive"))
      (node (ref "C5") (pin "1") (pinfunction "1_1") (pintype "passive"))
      (node (ref "C6") (pin "1") (pinfunction "1_1") (pintype "passive"))
      (node (ref "C7") (pin "1") (pinfunction "1_1") (pintype "passive"))
      (node (ref "C8") (pin "1") (pinfunction "1_1") (pintype "passive"))
      (node (ref "C9") (pin "1") (pinfunction "1_1") (pintype "passive"))
      (node (ref "D1") (pin "3") (pinfunction "A_3") (pintype "passive"))
      (node (ref "D10") (pin "1") (pinfunction "A_1") (pintype "passive"))
      (node (ref "D11") (pin "1") (pinfunction "A_1") (pintype "passive"))
      (node (ref "D12") (pin "1") (pinfunction "A_1") (pintype "passive"))
      (node (ref "D13") (pin "1") (pinfunction "A_1") (pintype "passive"))
      (node (ref "D14") (pin "1") (pinfunction "A_1") (pintype "passive"))
      (node (ref "D15") (pin "1") (pinfunction "A_1") (pintype "passive"))
      (node (ref "D16") (pin "1") (pinfunction "A_1") (pintype "passive"))
      (node (ref "D17") (pin "1") (pinfunction "A_1") (pintype "passive"))
      (node (ref "D18") (pin "1") (pinfunction "A_1") (pintype "passive"))
      (node (ref "D19") (pin "A") (pinfunction "A_A") (pintype "passive"))
      (node (ref "D2") (pin "A") (pinfunction "A_A") (pintype "passive"))
      (node (ref "D3") (pin "C") (pinfunction "C_C") (pintype "passive"))
      (node (ref "D4") (pin "C") (pinfunction "C_C") (pintype "passive"))
      (node (ref "D5") (pin "C") (pinfunction "C_C") (pintype "passive"))
      (node (ref "D6") (pin "C") (pinfunction "C_C") (pintype "passive"))
      (node (ref "D7") (pin "1") (pinfunction "A_1") (pintype "passive"))
      (node (ref "D8") (pin "C") (pinfunction "C_C") (pintype "passive"))
      (node (ref "D9") (pin "C") (pinfunction "C_C") (pintype "passive"))
      (node (ref "GND") (pin "1") (pinfunction "1_1") (pintype "passive"))
      (node (ref "GND") (pin "2") (pinfunction "2_2") (pintype "passive"))
      (node (ref "GND") (pin "3") (pinfunction "3_3") (pintype "passive"))
      (node (ref "GND") (pin "4") (pinfunction "4_4") (pintype "passive"))
      (node (ref "GND") (pin "5") (pinfunction "5_5") (pintype "passive"))
      (node (ref "GND") (pin "6") (pinfunction "6_6") (pintype "passive"))
      (node (ref "I1") (pin "1") (pinfunction "1_1") (pintype "passive"))
      (node (ref "I2") (pin "1") (pinfunction "1_1") (pintype "passive"))
      (node (ref "I3") (pin "1") (pinfunction "1_1") (pintype "passive"))
      (node (ref "I4") (pin "1") (pinfunction "1_1") (pintype "passive"))
      (node (ref "I5") (pin "1") (pinfunction "1_1") (pintype "passive"))
      (node (ref "IC1") (pin "18") (pinfunction "GND_18") (pintype "power_in"))
      (node (ref "IC1") (pin "35") (pinfunction "GND_35") (pintype "power_in"))
      (node (ref "IC1") (pin "42") (pinfunction "GND_42") (pintype "power_in"))
      (node (ref "IC1") (pin "5") (pinfunction "GND_5") (pintype "power_in"))
      (node (ref "IC1") (pin "TP") (pinfunction "GND_TP") (pintype "power_in"))
      (node (ref "IC2") (pin "4") (pinfunction "GND_4") (pintype "power_in"))
      (node (ref "IC3") (pin "10") (pinfunction "GND_10") (pintype "power_in"))
      (node (ref "IC4") (pin "1") (pinfunction "GND_1") (pintype "power_in"))
      (node (ref "IC5") (pin "4") (pinfunction "GNDA_4") (pintype "power_in"))
      (node (ref "IC5") (pin "6") (pinfunction "GND_6") (pintype "power_in"))
      (node (ref "IC6") (pin "1") (pinfunction "GND_1") (pintype "power_in"))
      (node (ref "IC7") (pin "1") (pinfunction "GND_1") (pintype "power_in"))
      (node (ref "IO1") (pin "1") (pinfunction "1_1") (pintype "passive"))
      (node (ref "IO2") (pin "1") (pinfunction "1_1") (pintype "passive"))
      (node (ref "J1") (pin "3") (pinfunction "3_3") (pintype "passive"))
      (node (ref "J2") (pin "1") (pinfunction "1_1") (pintype "passive"))
      (node (ref "PWR") (pin "1") (pinfunction "1_1") (pintype "passive"))
      (node (ref "R14") (pin "1") (pinfunction "1_1") (pintype "passive"))
      (node (ref "R15") (pin "2") (pinfunction "2_2") (pintype "passive"))
      (node (ref "R19") (pin "2") (pinfunction "2_2") (pintype "passive"))
      (node (ref "R26") (pin "2") (pinfunction "2_2") (pintype "passive"))
      (node (ref "R27") (pin "2") (pinfunction "2_2") (pintype "passive"))
      (node (ref "RESET") (pin "1") (pinfunction "P1_1") (pintype "passive"))
      (node (ref "RESET") (pin "4") (pinfunction "P1_4") (pintype "passive"))
      (node (ref "S1") (pin "1") (pinfunction "1_1") (pintype "passive"))
      (node (ref "S2") (pin "1") (pinfunction "1_1") (pintype "passive"))
      (node (ref "SW") (pin "2") (pinfunction "S1_2") (pintype "passive"))
      (node (ref "SW") (pin "3") (pinfunction "S1_3") (pintype "passive"))
      (node (ref "SWD") (pin "GND@1") (pinfunction "GND_GND@1") (pintype "power_in"))
      (node (ref "SWD") (pin "GND@2") (pinfunction "GND_GND@2") (pintype "power_in"))
      (node (ref "SWD") (pin "GND@3") (pinfunction "GND_GND@3") (pintype "power_in"))
      (node (ref "T4") (pin "1") (pinfunction "S_1") (pintype "passive"))
      (node (ref "T4") (pin "4") (pinfunction "S_4") (pintype "passive"))
      (node (ref "USB") (pin "GND") (pinfunction "GND_GND") (pintype "power_in"))
      (node (ref "XBEE1") (pin "10") (pinfunction "GND_10") (pintype "power_in"))
      (node (ref "XBEE2") (pin "10") (pinfunction "GND_10") (pintype "power_in"))
    )
    (net (code "36") (name "I2C_SCL") (class "Default")
      (node (ref "I1") (pin "4") (pinfunction "4_4") (pintype "passive"))
      (node (ref "I2") (pin "4") (pinfunction "4_4") (pintype "passive"))
      (node (ref "I3") (pin "4") (pinfunction "4_4") (pintype "passive"))
      (node (ref "I4") (pin "4") (pinfunction "4_4") (pintype "passive"))
      (node (ref "I5") (pin "4") (pinfunction "4_4") (pintype "passive"))
      (node (ref "R4") (pin "1") (pinfunction "1_1") (pintype "passive"))
      (node (ref "T5") (pin "6") (pinfunction "D_6") (pintype "passive"))
    )
    (net (code "37") (name "I2C_SDA") (class "Default")
      (node (ref "I1") (pin "3") (pinfunction "3_3") (pintype "passive"))
      (node (ref "I2") (pin "3") (pinfunction "3_3") (pintype "passive"))
      (node (ref "I3") (pin "3") (pinfunction "3_3") (pintype "passive"))
      (node (ref "I4") (pin "3") (pinfunction "3_3") (pintype "passive"))
      (node (ref "I5") (pin "3") (pinfunction "3_3") (pintype "passive"))
      (node (ref "R7") (pin "1") (pinfunction "1_1") (pintype "passive"))
      (node (ref "T5") (pin "3") (pinfunction "D_3") (pintype "passive"))
    )
    (net (code "38") (name "I2C_VCC") (class "Default")
      (node (ref "C5") (pin "2") (pinfunction "2_2") (pintype "passive"))
      (node (ref "I1") (pin "2") (pinfunction "2_2") (pintype "passive"))
      (node (ref "I2") (pin "2") (pinfunction "2_2") (pintype "passive"))
      (node (ref "I3") (pin "2") (pinfunction "2_2") (pintype "passive"))
      (node (ref "I4") (pin "2") (pinfunction "2_2") (pintype "passive"))
      (node (ref "I5") (pin "2") (pinfunction "2_2") (pintype "passive"))
      (node (ref "R31") (pin "2") (pinfunction "2_2") (pintype "passive"))
      (node (ref "R4") (pin "2") (pinfunction "2_2") (pintype "passive"))
      (node (ref "R7") (pin "2") (pinfunction "2_2") (pintype "passive"))
      (node (ref "T2") (pin "3") (pinfunction "D_3") (pintype "passive"))
    )
    (net (code "39") (name "IO1") (class "Default")
      (node (ref "IO") (pin "1") (pinfunction "1_1") (pintype "passive"))
      (node (ref "IO1") (pin "3") (pinfunction "3_3") (pintype "passive"))
      (node (ref "R40") (pin "2") (pinfunction "2_2") (pintype "passive"))
    )
    (net (code "40") (name "IO2") (class "Default")
      (node (ref "IO") (pin "2") (pinfunction "2_2") (pintype "passive"))
      (node (ref "IO1") (pin "4") (pinfunction "4_4") (pintype "passive"))
      (node (ref "R39") (pin "2") (pinfunction "2_2") (pintype "passive"))
    )
    (net (code "41") (name "IO3") (class "Default")
      (node (ref "IO") (pin "3") (pinfunction "3_3") (pintype "passive"))
      (node (ref "IO2") (pin "3") (pinfunction "3_3") (pintype "passive"))
      (node (ref "R42") (pin "2") (pinfunction "2_2") (pintype "passive"))
    )
    (net (code "42") (name "IO4") (class "Default")
      (node (ref "IO") (pin "4") (pinfunction "4_4") (pintype "passive"))
      (node (ref "IO2") (pin "4") (pinfunction "4_4") (pintype "passive"))
      (node (ref "R41") (pin "2") (pinfunction "2_2") (pintype "passive"))
    )
    (net (code "43") (name "IO5") (class "Default")
      (node (ref "IO") (pin "5") (pinfunction "5_5") (pintype "passive"))
      (node (ref "R30") (pin "2") (pinfunction "2_2") (pintype "passive"))
    )
    (net (code "44") (name "IO6") (class "Default")
      (node (ref "IO") (pin "6") (pinfunction "6_6") (pintype "passive"))
      (node (ref "R2") (pin "2") (pinfunction "2_2") (pintype "passive"))
    )
    (net (code "45") (name "Net-(D3-PadA)") (class "Default")
      (node (ref "D3") (pin "A") (pinfunction "A_A") (pintype "passive"))
      (node (ref "R22") (pin "2") (pinfunction "2_2") (pintype "passive"))
    )
    (net (code "46") (name "Net-(D4-PadA)") (class "Default")
      (node (ref "D4") (pin "A") (pinfunction "A_A") (pintype "passive"))
      (node (ref "R10") (pin "2") (pinfunction "2_2") (pintype "passive"))
    )
    (net (code "47") (name "Net-(D5-PadA)") (class "Default")
      (node (ref "D5") (pin "A") (pinfunction "A_A") (pintype "passive"))
      (node (ref "R28") (pin "1") (pinfunction "1_1") (pintype "passive"))
    )
    (net (code "48") (name "Net-(D6-PadA)") (class "Default")
      (node (ref "D6") (pin "A") (pinfunction "A_A") (pintype "passive"))
      (node (ref "R29") (pin "1") (pinfunction "1_1") (pintype "passive"))
    )
    (net (code "49") (name "Net-(D8-PadA)") (class "Default")
      (node (ref "D8") (pin "A") (pinfunction "A_A") (pintype "passive"))
      (node (ref "R31") (pin "1") (pinfunction "1_1") (pintype "passive"))
    )
    (net (code "50") (name "Net-(D9-PadA)") (class "Default")
      (node (ref "D9") (pin "A") (pinfunction "A_A") (pintype "passive"))
      (node (ref "R32") (pin "1") (pinfunction "1_1") (pintype "passive"))
    )
    (net (code "51") (name "Net-(F1-Pad1)") (class "Default")
      (node (ref "F1") (pin "1") (pinfunction "1_1") (pintype "passive"))
      (node (ref "USB") (pin "VBUS") (pinfunction "VBUS_VBUS") (pintype "power_in"))
    )
    (net (code "52") (name "Net-(F2-Pad1)") (class "Default")
      (node (ref "F2") (pin "1") (pinfunction "1_1") (pintype "passive"))
      (node (ref "PWR") (pin "2") (pinfunction "2_2") (pintype "passive"))
    )
    (net (code "53") (name "Net-(IC1-(XIN32{slash}S1:0{slash}T2:0)PA00)") (class "Default")
      (node (ref "C3") (pin "1") (pinfunction "1_1") (pintype "passive"))
      (node (ref "IC1") (pin "1") (pinfunction "(XIN32/S1:0/T2:0)PA00_1") (pintype "bidirectional"))
      (node (ref "Q1") (pin "2") (pinfunction "2_2") (pintype "passive"))
    )
    (net (code "54") (name "Net-(IC1-(XOUT32{slash}S1:1{slash}T2:1)PA01)") (class "Default")
      (node (ref "C4") (pin "2") (pinfunction "2_2") (pintype "passive"))
      (node (ref "IC1") (pin "2") (pinfunction "(XOUT32/S1:1/T2:1)PA01_2") (pintype "bidirectional"))
      (node (ref "Q1") (pin "1") (pinfunction "1_1") (pintype "passive"))
    )
    (net (code "55") (name "Net-(IC1-VCCANA)") (class "Default")
      (node (ref "C12") (pin "2") (pinfunction "2_2") (pintype "passive"))
      (node (ref "C16") (pin "2") (pinfunction "2_2") (pintype "passive"))
      (node (ref "C22") (pin "2") (pinfunction "2_2") (pintype "passive"))
      (node (ref "IC1") (pin "6") (pinfunction "VCCANA_6") (pintype "power_in"))
      (node (ref "L1") (pin "2") (pinfunction "2_2") (pintype "passive"))
    )
    (net (code "56") (name "Net-(IC1-VCCCORE)") (class "Default")
      (node (ref "C21") (pin "2") (pinfunction "2_2") (pintype "passive"))
      (node (ref "IC1") (pin "43") (pinfunction "VCCCORE_43") (pintype "power_in"))
    )
    (net (code "57") (name "Net-(IC3A-A1)") (class "Default")
      (node (ref "IC3") (pin "1") (pinfunction "G_1") (pintype "input"))
      (node (ref "IC3") (pin "2") (pinfunction "A1_2") (pintype "input"))
      (node (ref "R43") (pin "1") (pinfunction "1_1") (pintype "passive"))
      (node (ref "T8") (pin "6") (pinfunction "D_6") (pintype "passive"))
    )
    (net (code "58") (name "Net-(IC3B-A4)") (class "Default")
      (node (ref "IC3") (pin "17") (pinfunction "A4_17") (pintype "input"))
      (node (ref "IC3") (pin "19") (pinfunction "G_19") (pintype "input"))
      (node (ref "R44") (pin "1") (pinfunction "1_1") (pintype "passive"))
      (node (ref "T8") (pin "3") (pinfunction "D_3") (pintype "passive"))
    )
    (net (code "59") (name "Net-(IC5-SDO1)") (class "Default")
      (node (ref "IC5") (pin "17") (pinfunction "SDO1_17") (pintype "bidirectional"))
      (node (ref "J1") (pin "2") (pinfunction "2_2") (pintype "passive"))
    )
    (net (code "60") (name "Net-(IC5-SDO2)") (class "Default")
      (node (ref "IC5") (pin "12") (pinfunction "SDO2_12") (pintype "bidirectional"))
      (node (ref "J2") (pin "2") (pinfunction "2_2") (pintype "passive"))
    )
    (net (code "61") (name "Net-(IC6-RST)") (class "Default")
      (node (ref "IC6") (pin "2") (pinfunction "RST_2") (pintype "output"))
      (node (ref "XBEE2") (pin "5") (pinfunction "~{RESET}_5") (pintype "bidirectional"))
    )
    (net (code "62") (name "Net-(IC7-RST)") (class "Default")
      (node (ref "IC7") (pin "2") (pinfunction "RST_2") (pintype "output"))
      (node (ref "XBEE1") (pin "5") (pinfunction "~{RESET}_5") (pintype "bidirectional"))
    )
    (net (code "63") (name "Net-(R1-Pad2)") (class "Default")
      (node (ref "R1") (pin "2") (pinfunction "2_2") (pintype "passive"))
      (node (ref "SW") (pin "1") (pinfunction "P1_1") (pintype "passive"))
      (node (ref "SW") (pin "4") (pinfunction "P1_4") (pintype "passive"))
    )
    (net (code "64") (name "Net-(R14-Pad2)") (class "Default")
      (node (ref "R14") (pin "2") (pinfunction "2_2") (pintype "passive"))
      (node (ref "USB") (pin "SHLD1") (pinfunction "SHIELD_SHLD1") (pintype "passive"))
      (node (ref "USB") (pin "SHLD2") (pinfunction "SHIELD_SHLD2") (pintype "passive"))
      (node (ref "USB") (pin "SHLD3") (pinfunction "SHIELD_SHLD3") (pintype "passive"))
      (node (ref "USB") (pin "SHLD4") (pinfunction "SHIELD_SHLD4") (pintype "passive"))
      (node (ref "USB") (pin "SHLD5") (pinfunction "SHIELD_SHLD5") (pintype "passive"))
      (node (ref "USB") (pin "SHLD6") (pinfunction "SHIELD_SHLD6") (pintype "passive"))
      (node (ref "USB") (pin "SHLD7") (pinfunction "SHIELD_SHLD7") (pintype "passive"))
      (node (ref "USB") (pin "SHLD8") (pinfunction "SHIELD_SHLD8") (pintype "passive"))
    )
    (net (code "65") (name "Net-(R25-Pad2)") (class "Default")
      (node (ref "R25") (pin "2") (pinfunction "2_2") (pintype "passive"))
      (node (ref "RESET") (pin "2") (pinfunction "S1_2") (pintype "passive"))
      (node (ref "RESET") (pin "3") (pinfunction "S1_3") (pintype "passive"))
    )
    (net (code "66") (name "Net-(R35-Pad2)") (class "Default")
      (node (ref "R35") (pin "2") (pinfunction "2_2") (pintype "passive"))
      (node (ref "S1") (pin "4") (pinfunction "4_4") (pintype "passive"))
    )
    (net (code "67") (name "Net-(R36-Pad2)") (class "Default")
      (node (ref "R36") (pin "2") (pinfunction "2_2") (pintype "passive"))
      (node (ref "S1") (pin "3") (pinfunction "3_3") (pintype "passive"))
    )
    (net (code "68") (name "Net-(R37-Pad2)") (class "Default")
      (node (ref "R37") (pin "2") (pinfunction "2_2") (pintype "passive"))
      (node (ref "S2") (pin "4") (pinfunction "4_4") (pintype "passive"))
    )
    (net (code "69") (name "Net-(R38-Pad2)") (class "Default")
      (node (ref "R38") (pin "2") (pinfunction "2_2") (pintype "passive"))
      (node (ref "S2") (pin "3") (pinfunction "3_3") (pintype "passive"))
    )
    (net (code "70") (name "Net-(T2-G)") (class "Default")
      (node (ref "R8") (pin "2") (pinfunction "2_2") (pintype "passive"))
      (node (ref "T2") (pin "1") (pinfunction "G_1") (pintype "passive"))
      (node (ref "T4") (pin "6") (pinfunction "D_6") (pintype "passive"))
    )
    (net (code "71") (name "Net-(T3-G)") (class "Default")
      (node (ref "R9") (pin "2") (pinfunction "2_2") (pintype "passive"))
      (node (ref "T3") (pin "1") (pinfunction "G_1") (pintype "passive"))
      (node (ref "T4") (pin "3") (pinfunction "D_3") (pintype "passive"))
    )
    (net (code "72") (name "Net-(XBEE1-DIN{slash}RX{slash}~{CFG})") (class "Default")
      (node (ref "R12") (pin "2") (pinfunction "2_2") (pintype "passive"))
      (node (ref "XBEE1") (pin "3") (pinfunction "DIN/RX/~{CFG}_3") (pintype "bidirectional"))
    )
    (net (code "73") (name "Net-(XBEE1-DIO7{slash}CTS)") (class "Default")
      (node (ref "R13") (pin "1") (pinfunction "1_1") (pintype "passive"))
      (node (ref "XBEE1") (pin "12") (pinfunction "DIO7/CTS_12") (pintype "bidirectional"))
    )
    (net (code "74") (name "Net-(XBEE1-DOUT{slash}TX)") (class "Default")
      (node (ref "R11") (pin "2") (pinfunction "2_2") (pintype "passive"))
      (node (ref "XBEE1") (pin "2") (pinfunction "DOUT/TX_2") (pintype "bidirectional"))
    )
    (net (code "75") (name "Net-(XBEE2-DIN{slash}RX{slash}~{CFG})") (class "Default")
      (node (ref "R20") (pin "2") (pinfunction "2_2") (pintype "passive"))
      (node (ref "XBEE2") (pin "3") (pinfunction "DIN/RX/~{CFG}_3") (pintype "bidirectional"))
    )
    (net (code "76") (name "Net-(XBEE2-DIO7{slash}CTS)") (class "Default")
      (node (ref "R18") (pin "1") (pinfunction "1_1") (pintype "passive"))
      (node (ref "XBEE2") (pin "12") (pinfunction "DIO7/CTS_12") (pintype "bidirectional"))
    )
    (net (code "77") (name "Net-(XBEE2-DOUT{slash}TX)") (class "Default")
      (node (ref "R21") (pin "2") (pinfunction "2_2") (pintype "passive"))
      (node (ref "XBEE2") (pin "2") (pinfunction "DOUT/TX_2") (pintype "bidirectional"))
    )
    (net (code "78") (name "RST") (class "Default")
      (node (ref "C1") (pin "2") (pinfunction "2_2") (pintype "passive"))
      (node (ref "IC1") (pin "40") (pinfunction "~{RESET}_40") (pintype "input"))
      (node (ref "R24") (pin "2") (pinfunction "2_2") (pintype "passive"))
      (node (ref "R25") (pin "1") (pinfunction "1_1") (pintype "passive"))
      (node (ref "SWD") (pin "RST") (pinfunction "RST_RST") (pintype "bidirectional"))
    )
    (net (code "79") (name "SWCLK") (class "Default")
      (node (ref "IC1") (pin "45") (pinfunction "(SWCLK/S1:2/T1:0)PA30_45") (pintype "bidirectional"))
      (node (ref "R33") (pin "2") (pinfunction "2_2") (pintype "passive"))
      (node (ref "SWD") (pin "SWCLK") (pinfunction "SWCLK_SWCLK") (pintype "bidirectional"))
    )
    (net (code "80") (name "SWDIO") (class "Default")
      (node (ref "IC1") (pin "46") (pinfunction "(SWDIO/S1:3/T1:1)PA31_46") (pintype "bidirectional"))
      (node (ref "SWD") (pin "SWDIO") (pinfunction "SWDIO_SWDIO") (pintype "bidirectional"))
    )
    (net (code "81") (name "UART_VCC") (class "Default")
      (node (ref "C6") (pin "2") (pinfunction "2_2") (pintype "passive"))
      (node (ref "R32") (pin "2") (pinfunction "2_2") (pintype "passive"))
      (node (ref "S1") (pin "2") (pinfunction "2_2") (pintype "passive"))
      (node (ref "S2") (pin "2") (pinfunction "2_2") (pintype "passive"))
      (node (ref "T3") (pin "3") (pinfunction "D_3") (pintype "passive"))
    )
    (net (code "82") (name "USB_D_N") (class "Default")
      (node (ref "D1") (pin "1") (pinfunction "C1_1") (pintype "passive"))
      (node (ref "IC1") (pin "33") (pinfunction "(USBM/S3:2|5:2/T5:0|1:2)PA24_33") (pintype "bidirectional"))
      (node (ref "USB") (pin "D-") (pinfunction "D-_D-") (pintype "bidirectional"))
    )
    (net (code "83") (name "USB_D_P") (class "Default")
      (node (ref "D1") (pin "2") (pinfunction "C2_2") (pintype "passive"))
      (node (ref "IC1") (pin "34") (pinfunction "(USBP/S3:3|5:3/T5:1|1:3)PA25_34") (pintype "bidirectional"))
      (node (ref "USB") (pin "D+") (pinfunction "D+_D+") (pintype "bidirectional"))
    )
    (net (code "84") (name "XB1_CS") (class "Default")
      (node (ref "IC3") (pin "18") (pinfunction "Y1_18") (pintype "tri_state"))
      (node (ref "R46") (pin "1") (pinfunction "1_1") (pintype "passive"))
      (node (ref "XBEE1") (pin "17") (pinfunction "AD3/DIO3/SS_17") (pintype "bidirectional"))
    )
    (net (code "85") (name "XB1_MISO") (class "Default")
      (node (ref "IC3") (pin "8") (pinfunction "A4_8") (pintype "input"))
      (node (ref "XBEE1") (pin "4") (pinfunction "MISO/DIO12_4") (pintype "bidirectional"))
    )
    (net (code "86") (name "XB1_MOSI") (class "Default")
      (node (ref "IC3") (pin "16") (pinfunction "Y2_16") (pintype "tri_state"))
      (node (ref "XBEE1") (pin "11") (pinfunction "DIO4/MOSI_11") (pintype "bidirectional"))
    )
    (net (code "87") (name "XB1_SCK") (class "Default")
      (node (ref "IC3") (pin "14") (pinfunction "Y3_14") (pintype "tri_state"))
      (node (ref "XBEE1") (pin "18") (pinfunction "AD2/DIO2/SCK_18") (pintype "bidirectional"))
    )
    (net (code "88") (name "XB1_VCC") (class "Default")
      (node (ref "C14") (pin "2") (pinfunction "2_2") (pintype "passive"))
      (node (ref "C15") (pin "2") (pinfunction "2_2") (pintype "passive"))
      (node (ref "C2") (pin "2") (pinfunction "2_2") (pintype "passive"))
      (node (ref "IC7") (pin "3") (pinfunction "VCC_3") (pintype "power_in"))
      (node (ref "R15") (pin "1") (pinfunction "1_1") (pintype "passive"))
      (node (ref "R28") (pin "2") (pinfunction "2_2") (pintype "passive"))
      (node (ref "R46") (pin "2") (pinfunction "2_2") (pintype "passive"))
      (node (ref "T7") (pin "3") (pinfunction "D_3") (pintype "passive"))
      (node (ref "T8") (pin "2") (pinfunction "G_2") (pintype "passive"))
      (node (ref "XBEE1") (pin "1") (pinfunction "VCC_1") (pintype "power_in"))
    )
    (net (code "89") (name "XB2_CS") (class "Default")
      (node (ref "IC3") (pin "3") (pinfunction "Y4_3") (pintype "tri_state"))
      (node (ref "R45") (pin "1") (pinfunction "1_1") (pintype "passive"))
      (node (ref "XBEE2") (pin "17") (pinfunction "AD3/DIO3/SS_17") (pintype "bidirectional"))
    )
    (net (code "90") (name "XB2_MISO") (class "Default")
      (node (ref "IC3") (pin "11") (pinfunction "A1_11") (pintype "input"))
      (node (ref "XBEE2") (pin "4") (pinfunction "MISO/DIO12_4") (pintype "bidirectional"))
    )
    (net (code "91") (name "XB2_MOSI") (class "Default")
      (node (ref "IC3") (pin "7") (pinfunction "Y2_7") (pintype "tri_state"))
      (node (ref "XBEE2") (pin "11") (pinfunction "DIO4/MOSI_11") (pintype "bidirectional"))
    )
    (net (code "92") (name "XB2_SCK") (class "Default")
      (node (ref "IC3") (pin "5") (pinfunction "Y3_5") (pintype "tri_state"))
      (node (ref "XBEE2") (pin "18") (pinfunction "AD2/DIO2/SCK_18") (pintype "bidirectional"))
    )
    (net (code "93") (name "XB2_VCC") (class "Default")
      (node (ref "C17") (pin "2") (pinfunction "2_2") (pintype "passive"))
      (node (ref "C18") (pin "2") (pinfunction "2_2") (pintype "passive"))
      (node (ref "C19") (pin "2") (pinfunction "2_2") (pintype "passive"))
      (node (ref "IC6") (pin "3") (pinfunction "VCC_3") (pintype "power_in"))
      (node (ref "R19") (pin "1") (pinfunction "1_1") (pintype "passive"))
      (node (ref "R29") (pin "2") (pinfunction "2_2") (pintype "passive"))
      (node (ref "R45") (pin "2") (pinfunction "2_2") (pintype "passive"))
      (node (ref "T6") (pin "3") (pinfunction "D_3") (pintype "passive"))
      (node (ref "T8") (pin "5") (pinfunction "G_5") (pintype "passive"))
      (node (ref "XBEE2") (pin "1") (pinfunction "VCC_1") (pintype "power_in"))
    )
    (net (code "94") (name "unconnected-(IC5-CSB1-Pad16)") (class "Default")
      (node (ref "IC5") (pin "16") (pinfunction "CSB1_16") (pintype "bidirectional"))
    )
    (net (code "95") (name "unconnected-(IC5-CSB2-Pad5)") (class "Default")
      (node (ref "IC5") (pin "5") (pinfunction "CSB2_5") (pintype "bidirectional"))
    )
    (net (code "96") (name "unconnected-(IC5-CSB3-Pad20)") (class "Default")
      (node (ref "IC5") (pin "20") (pinfunction "CSB3_20") (pintype "bidirectional"))
    )
    (net (code "97") (name "unconnected-(IC5-DRDYM-Pad2)") (class "Default")
      (node (ref "IC5") (pin "2") (pinfunction "DRDYM_2") (pintype "bidirectional"))
    )
    (net (code "98") (name "unconnected-(IC5-INT1-Pad19)") (class "Default")
      (node (ref "IC5") (pin "19") (pinfunction "INT1_19") (pintype "output"))
    )
    (net (code "99") (name "unconnected-(IC5-INT2-Pad1)") (class "Default")
      (node (ref "IC5") (pin "1") (pinfunction "INT2_1") (pintype "output"))
    )
    (net (code "100") (name "unconnected-(IC5-INT3-Pad14)") (class "Default")
      (node (ref "IC5") (pin "14") (pinfunction "INT3_14") (pintype "output"))
    )
    (net (code "101") (name "unconnected-(IC5-INT4-Pad15)") (class "Default")
      (node (ref "IC5") (pin "15") (pinfunction "INT4_15") (pintype "output"))
    )
    (net (code "102") (name "unconnected-(IC5-INT5-Pad10)") (class "Default")
      (node (ref "IC5") (pin "10") (pinfunction "INT5_10") (pintype "bidirectional"))
    )
    (net (code "103") (name "unconnected-(XBEE1-AD0{slash}DIO0{slash}SDA{slash}CB-Pad20)") (class "Default")
      (node (ref "XBEE1") (pin "20") (pinfunction "AD0/DIO0/SDA/CB_20") (pintype "bidirectional"))
    )
    (net (code "104") (name "unconnected-(XBEE1-AD1{slash}DIO1{slash}SCL{slash}ATTN-Pad19)") (class "Default")
      (node (ref "XBEE1") (pin "19") (pinfunction "AD1/DIO1/SCL/ATTN_19") (pintype "bidirectional"))
    )
    (net (code "105") (name "unconnected-(XBEE1-DIO5{slash}ASSC-Pad15)") (class "Default")
      (node (ref "XBEE1") (pin "15") (pinfunction "DIO5/ASSC_15") (pintype "bidirectional"))
    )
    (net (code "106") (name "unconnected-(XBEE1-DIO6{slash}RTS-Pad16)") (class "Default")
      (node (ref "XBEE1") (pin "16") (pinfunction "DIO6/RTS_16") (pintype "bidirectional"))
    )
    (net (code "107") (name "unconnected-(XBEE1-DIO9{slash}ON_~{SLEEP}-Pad13)") (class "Default")
      (node (ref "XBEE1") (pin "13") (pinfunction "DIO9/ON_~{SLEEP}_13") (pintype "bidirectional"))
    )
    (net (code "108") (name "unconnected-(XBEE1-DTR{slash}DIO8-Pad9)") (class "Default")
      (node (ref "XBEE1") (pin "9") (pinfunction "DTR/DIO8_9") (pintype "bidirectional"))
    )
    (net (code "109") (name "unconnected-(XBEE1-PWM1{slash}DIO11-Pad7)") (class "Default")
      (node (ref "XBEE1") (pin "7") (pinfunction "PWM1/DIO11_7") (pintype "bidirectional"))
    )
    (net (code "110") (name "unconnected-(XBEE1-RES-Pad8)") (class "Default")
      (node (ref "XBEE1") (pin "8") (pinfunction "RES_8") (pintype "bidirectional"))
    )
    (net (code "111") (name "unconnected-(XBEE1-RSSI{slash}PWM0{slash}DIO10-Pad6)") (class "Default")
      (node (ref "XBEE1") (pin "6") (pinfunction "RSSI/PWM0/DIO10_6") (pintype "bidirectional"))
    )
    (net (code "112") (name "unconnected-(XBEE1-VREF-Pad14)") (class "Default")
      (node (ref "XBEE1") (pin "14") (pinfunction "VREF_14") (pintype "bidirectional"))
    )
    (net (code "113") (name "unconnected-(XBEE2-AD0{slash}DIO0{slash}SDA{slash}CB-Pad20)") (class "Default")
      (node (ref "XBEE2") (pin "20") (pinfunction "AD0/DIO0/SDA/CB_20") (pintype "bidirectional"))
    )
    (net (code "114") (name "unconnected-(XBEE2-AD1{slash}DIO1{slash}SCL{slash}ATTN-Pad19)") (class "Default")
      (node (ref "XBEE2") (pin "19") (pinfunction "AD1/DIO1/SCL/ATTN_19") (pintype "bidirectional"))
    )
    (net (code "115") (name "unconnected-(XBEE2-DIO5{slash}ASSC-Pad15)") (class "Default")
      (node (ref "XBEE2") (pin "15") (pinfunction "DIO5/ASSC_15") (pintype "bidirectional"))
    )
    (net (code "116") (name "unconnected-(XBEE2-DIO6{slash}RTS-Pad16)") (class "Default")
      (node (ref "XBEE2") (pin "16") (pinfunction "DIO6/RTS_16") (pintype "bidirectional"))
    )
    (net (code "117") (name "unconnected-(XBEE2-DIO9{slash}ON_~{SLEEP}-Pad13)") (class "Default")
      (node (ref "XBEE2") (pin "13") (pinfunction "DIO9/ON_~{SLEEP}_13") (pintype "bidirectional"))
    )
    (net (code "118") (name "unconnected-(XBEE2-DTR{slash}DIO8-Pad9)") (class "Default")
      (node (ref "XBEE2") (pin "9") (pinfunction "DTR/DIO8_9") (pintype "bidirectional"))
    )
    (net (code "119") (name "unconnected-(XBEE2-PWM1{slash}DIO11-Pad7)") (class "Default")
      (node (ref "XBEE2") (pin "7") (pinfunction "PWM1/DIO11_7") (pintype "bidirectional"))
    )
    (net (code "120") (name "unconnected-(XBEE2-RES-Pad8)") (class "Default")
      (node (ref "XBEE2") (pin "8") (pinfunction "RES_8") (pintype "bidirectional"))
    )
    (net (code "121") (name "unconnected-(XBEE2-RSSI{slash}PWM0{slash}DIO10-Pad6)") (class "Default")
      (node (ref "XBEE2") (pin "6") (pinfunction "RSSI/PWM0/DIO10_6") (pintype "bidirectional"))
    )
    (net (code "122") (name "unconnected-(XBEE2-VREF-Pad14)") (class "Default")
      (node (ref "XBEE2") (pin "14") (pinfunction "VREF_14") (pintype "bidirectional"))
    )
  )
)
